# alu.net
KiCad netlist of a schematic drawn in EAGLE
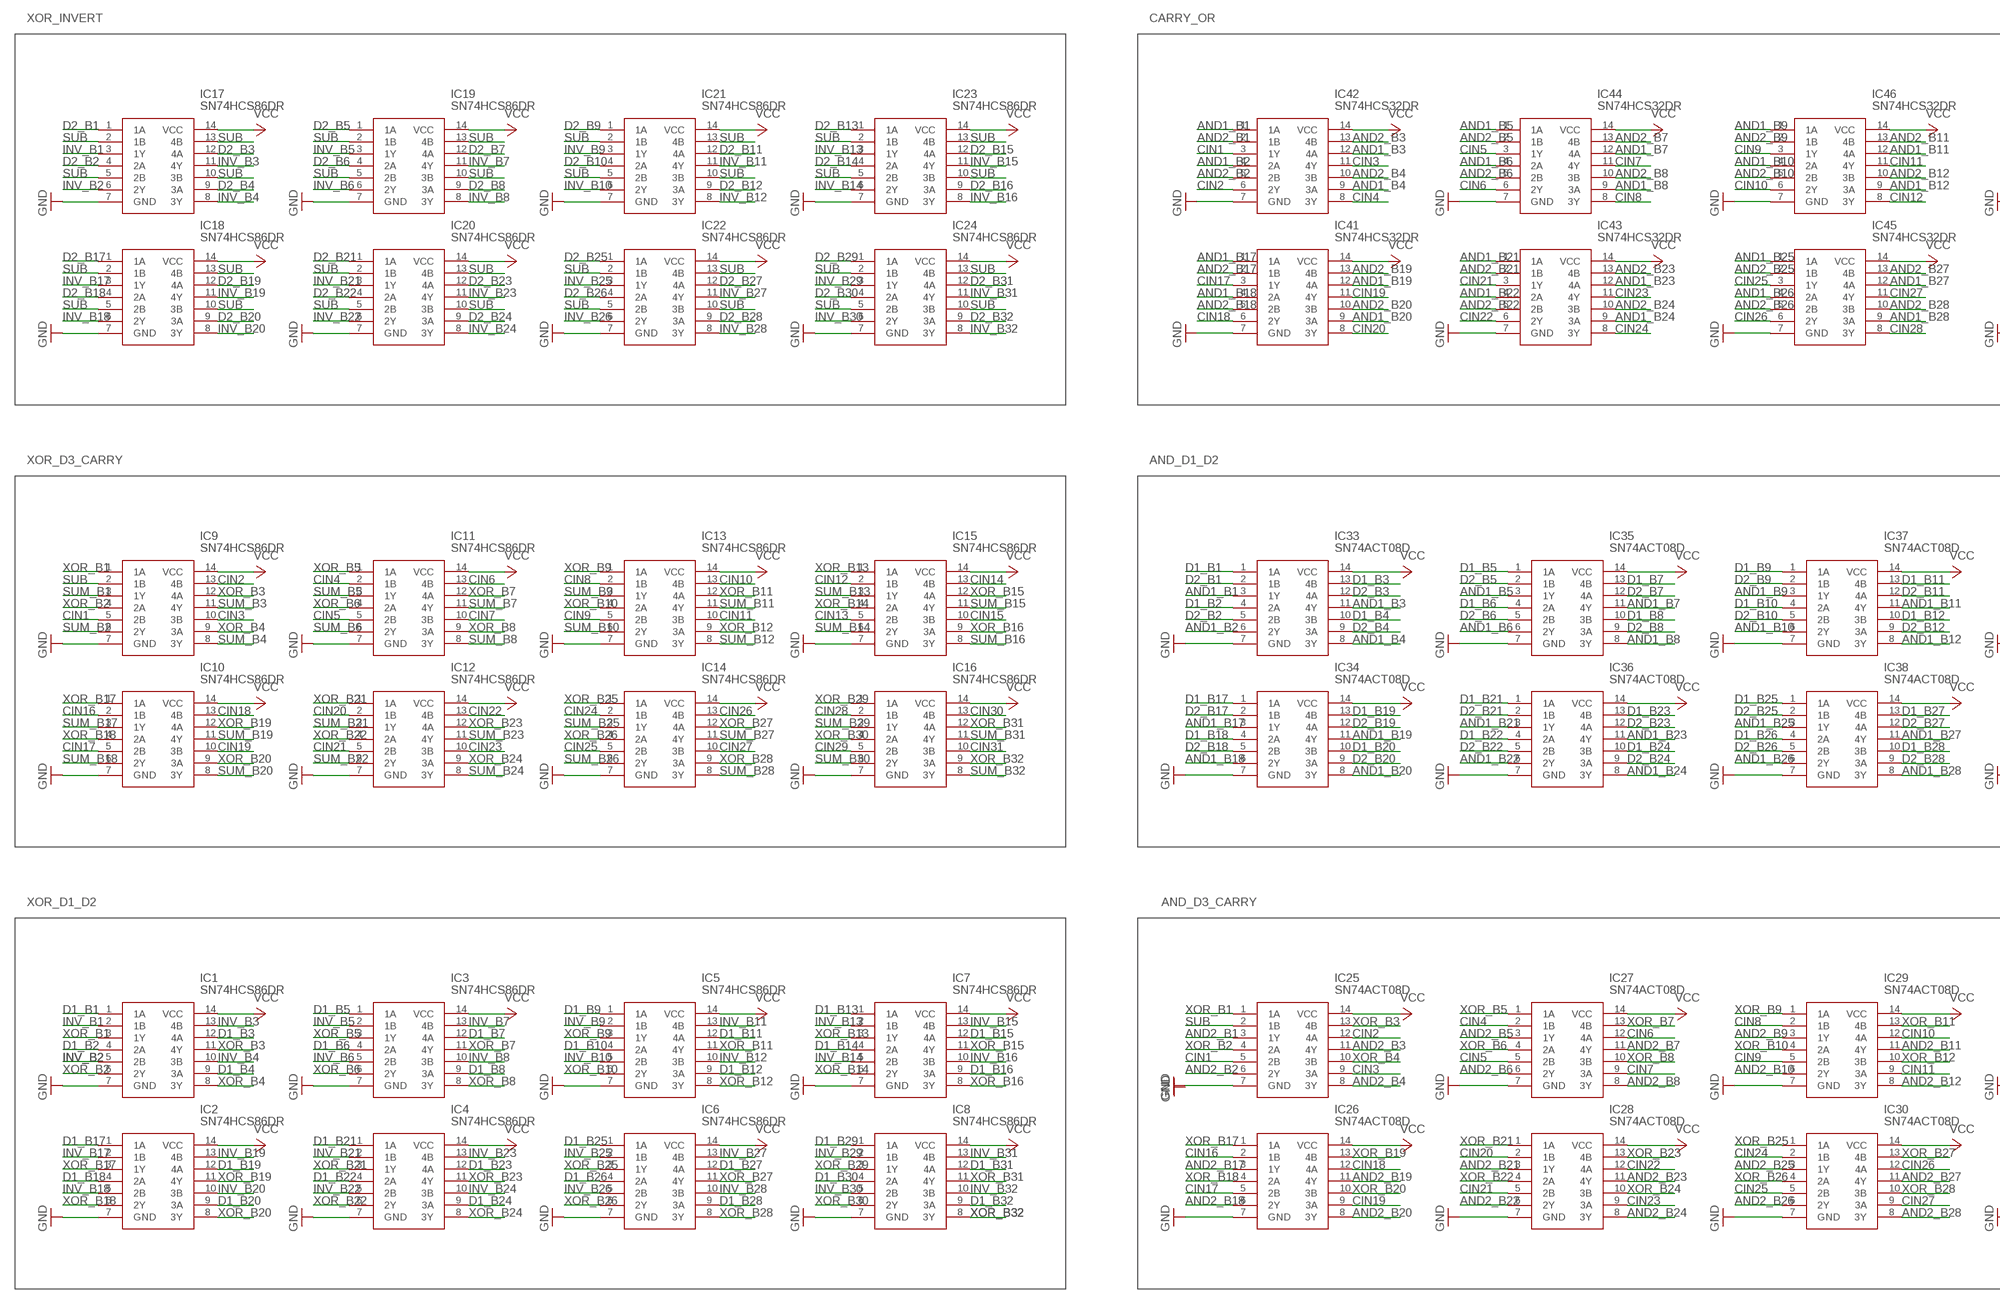
[diagram p0: schematic, sheet 1, part 1 of 2]
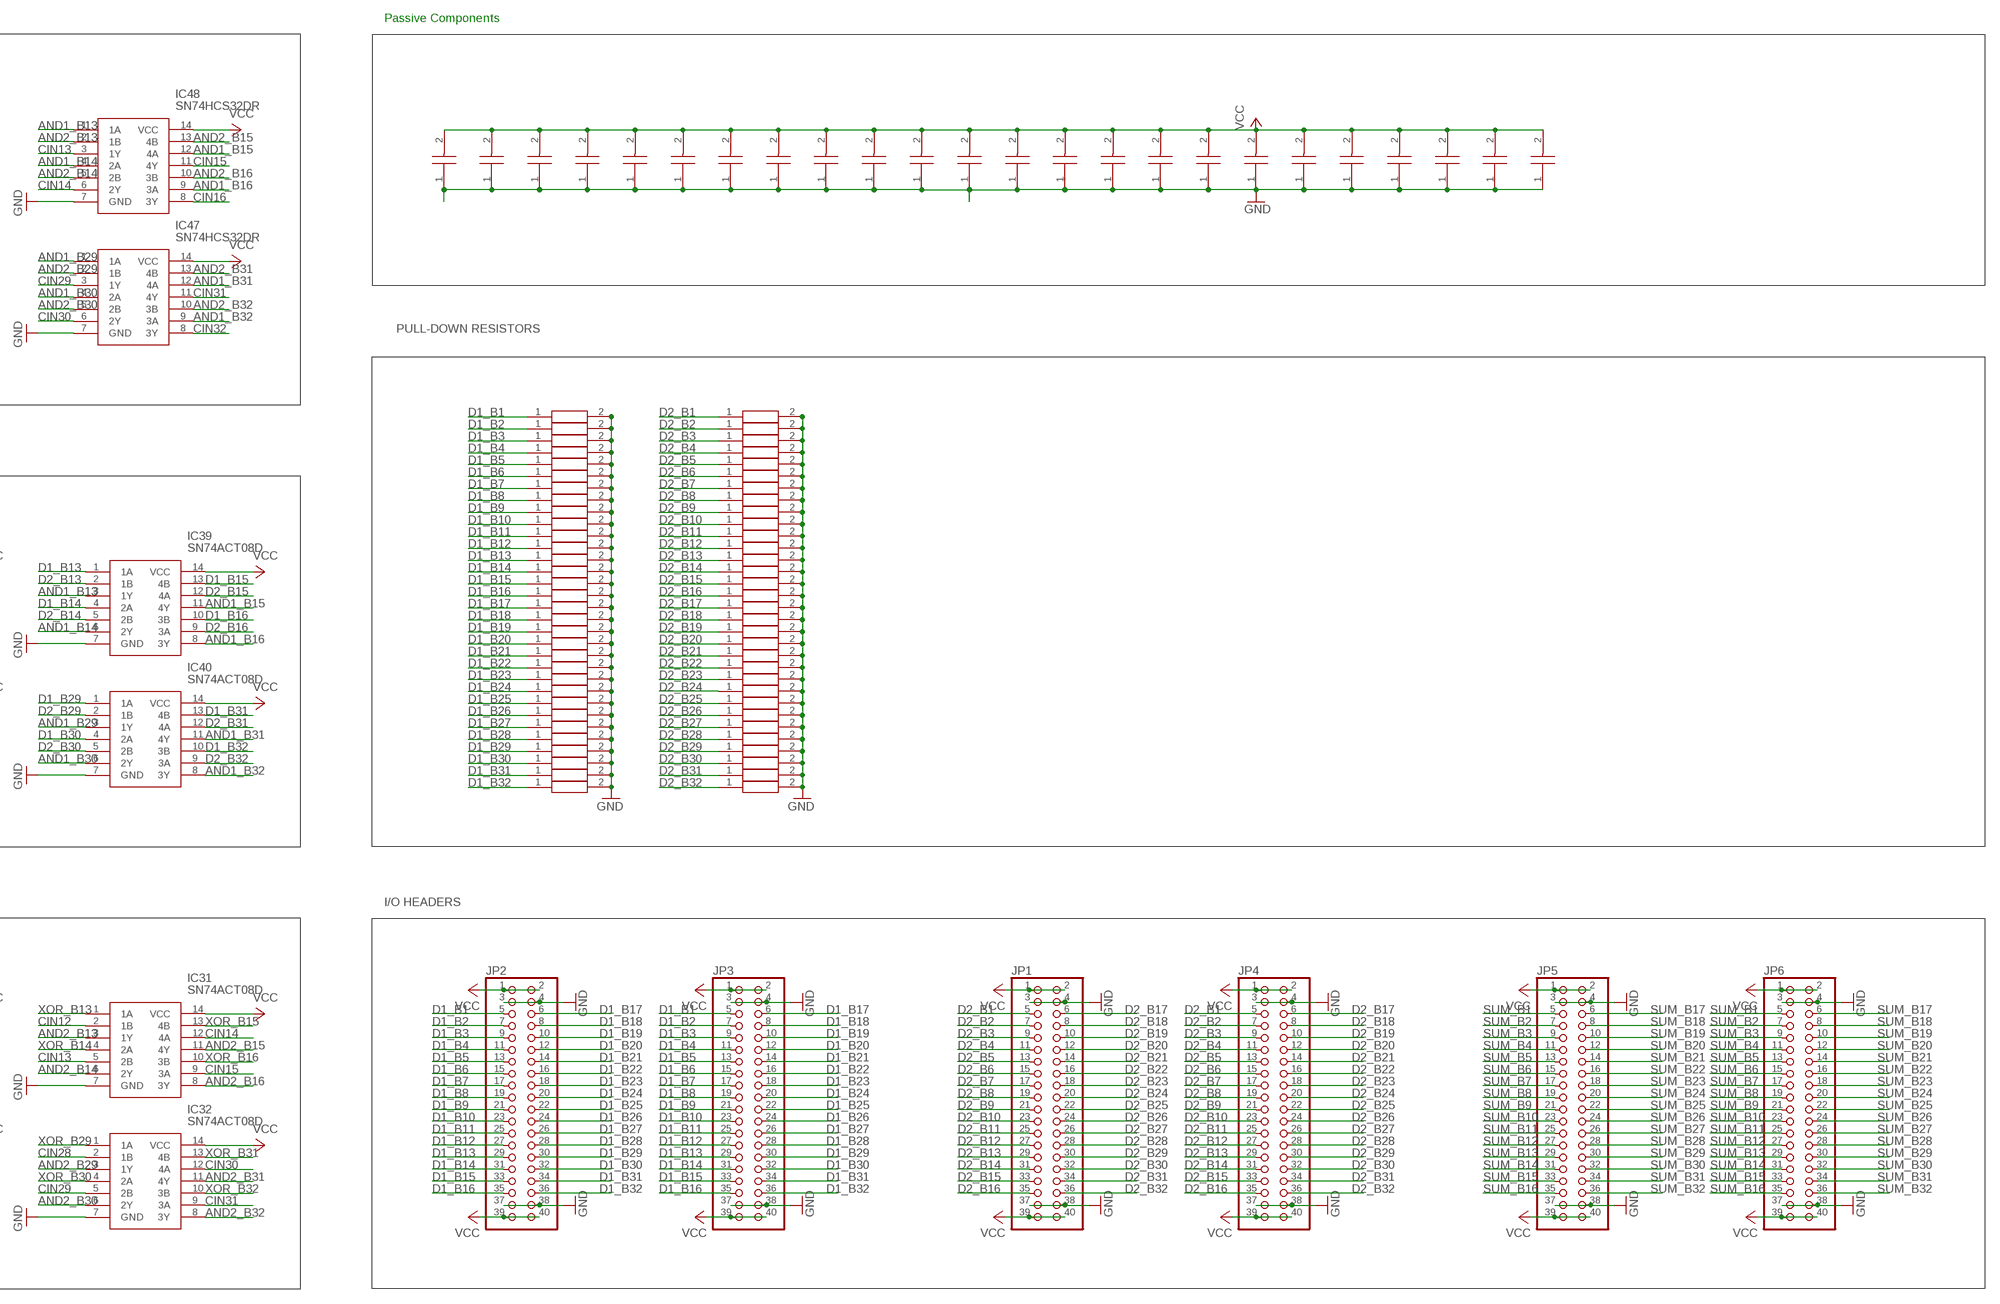
[diagram p1: schematic, sheet 1, part 2 of 2]

(export (version "E")
  (design (tool "Eeschema 10.0.6"))
  (components
    (comp (ref "C1")
      (value "CC0603KRX7R9BB104")
      (footprint "eagle-import:CAPC1608X90N")
      (fields (field (name "MOUSER_PART_NUMBER") "603-CC603KRX7R9BB104"))
      (libsource (lib "eagle-import") (part "CC0603KRX7R9BB104"))
    )
    (comp (ref "C2")
      (value "CC0603KRX7R9BB104")
      (footprint "eagle-import:CAPC1608X90N")
      (fields (field (name "MOUSER_PART_NUMBER") "603-CC603KRX7R9BB104"))
      (libsource (lib "eagle-import") (part "CC0603KRX7R9BB104"))
    )
    (comp (ref "C3")
      (value "CC0603KRX7R9BB104")
      (footprint "eagle-import:CAPC1608X90N")
      (fields (field (name "MOUSER_PART_NUMBER") "603-CC603KRX7R9BB104"))
      (libsource (lib "eagle-import") (part "CC0603KRX7R9BB104"))
    )
    (comp (ref "C4")
      (value "CC0603KRX7R9BB104")
      (footprint "eagle-import:CAPC1608X90N")
      (fields (field (name "MOUSER_PART_NUMBER") "603-CC603KRX7R9BB104"))
      (libsource (lib "eagle-import") (part "CC0603KRX7R9BB104"))
    )
    (comp (ref "C5")
      (value "CC0603KRX7R9BB104")
      (footprint "eagle-import:CAPC1608X90N")
      (fields (field (name "MOUSER_PART_NUMBER") "603-CC603KRX7R9BB104"))
      (libsource (lib "eagle-import") (part "CC0603KRX7R9BB104"))
    )
    (comp (ref "C6")
      (value "CC0603KRX7R9BB104")
      (footprint "eagle-import:CAPC1608X90N")
      (fields (field (name "MOUSER_PART_NUMBER") "603-CC603KRX7R9BB104"))
      (libsource (lib "eagle-import") (part "CC0603KRX7R9BB104"))
    )
    (comp (ref "C7")
      (value "CC0603KRX7R9BB104")
      (footprint "eagle-import:CAPC1608X90N")
      (fields (field (name "MOUSER_PART_NUMBER") "603-CC603KRX7R9BB104"))
      (libsource (lib "eagle-import") (part "CC0603KRX7R9BB104"))
    )
    (comp (ref "C8")
      (value "CC0603KRX7R9BB104")
      (footprint "eagle-import:CAPC1608X90N")
      (fields (field (name "MOUSER_PART_NUMBER") "603-CC603KRX7R9BB104"))
      (libsource (lib "eagle-import") (part "CC0603KRX7R9BB104"))
    )
    (comp (ref "C9")
      (value "CC0603KRX7R9BB104")
      (footprint "eagle-import:CAPC1608X90N")
      (fields (field (name "MOUSER_PART_NUMBER") "603-CC603KRX7R9BB104"))
      (libsource (lib "eagle-import") (part "CC0603KRX7R9BB104"))
    )
    (comp (ref "C10")
      (value "CC0603KRX7R9BB104")
      (footprint "eagle-import:CAPC1608X90N")
      (fields (field (name "MOUSER_PART_NUMBER") "603-CC603KRX7R9BB104"))
      (libsource (lib "eagle-import") (part "CC0603KRX7R9BB104"))
    )
    (comp (ref "C11")
      (value "CC0603KRX7R9BB104")
      (footprint "eagle-import:CAPC1608X90N")
      (fields (field (name "MOUSER_PART_NUMBER") "603-CC603KRX7R9BB104"))
      (libsource (lib "eagle-import") (part "CC0603KRX7R9BB104"))
    )
    (comp (ref "C12")
      (value "CC0603KRX7R9BB104")
      (footprint "eagle-import:CAPC1608X90N")
      (fields (field (name "MOUSER_PART_NUMBER") "603-CC603KRX7R9BB104"))
      (libsource (lib "eagle-import") (part "CC0603KRX7R9BB104"))
    )
    (comp (ref "C13")
      (value "CC0603KRX7R9BB104")
      (footprint "eagle-import:CAPC1608X90N")
      (fields (field (name "MOUSER_PART_NUMBER") "603-CC603KRX7R9BB104"))
      (libsource (lib "eagle-import") (part "CC0603KRX7R9BB104"))
    )
    (comp (ref "C14")
      (value "CC0603KRX7R9BB104")
      (footprint "eagle-import:CAPC1608X90N")
      (fields (field (name "MOUSER_PART_NUMBER") "603-CC603KRX7R9BB104"))
      (libsource (lib "eagle-import") (part "CC0603KRX7R9BB104"))
    )
    (comp (ref "C15")
      (value "CC0603KRX7R9BB104")
      (footprint "eagle-import:CAPC1608X90N")
      (fields (field (name "MOUSER_PART_NUMBER") "603-CC603KRX7R9BB104"))
      (libsource (lib "eagle-import") (part "CC0603KRX7R9BB104"))
    )
    (comp (ref "C16")
      (value "CC0603KRX7R9BB104")
      (footprint "eagle-import:CAPC1608X90N")
      (fields (field (name "MOUSER_PART_NUMBER") "603-CC603KRX7R9BB104"))
      (libsource (lib "eagle-import") (part "CC0603KRX7R9BB104"))
    )
    (comp (ref "C17")
      (value "CC0603KRX7R9BB104")
      (footprint "eagle-import:CAPC1608X90N")
      (fields (field (name "MOUSER_PART_NUMBER") "603-CC603KRX7R9BB104"))
      (libsource (lib "eagle-import") (part "CC0603KRX7R9BB104"))
    )
    (comp (ref "C18")
      (value "CC0603KRX7R9BB104")
      (footprint "eagle-import:CAPC1608X90N")
      (fields (field (name "MOUSER_PART_NUMBER") "603-CC603KRX7R9BB104"))
      (libsource (lib "eagle-import") (part "CC0603KRX7R9BB104"))
    )
    (comp (ref "C19")
      (value "CC0603KRX7R9BB104")
      (footprint "eagle-import:CAPC1608X90N")
      (fields (field (name "MOUSER_PART_NUMBER") "603-CC603KRX7R9BB104"))
      (libsource (lib "eagle-import") (part "CC0603KRX7R9BB104"))
    )
    (comp (ref "C20")
      (value "CC0603KRX7R9BB104")
      (footprint "eagle-import:CAPC1608X90N")
      (fields (field (name "MOUSER_PART_NUMBER") "603-CC603KRX7R9BB104"))
      (libsource (lib "eagle-import") (part "CC0603KRX7R9BB104"))
    )
    (comp (ref "C21")
      (value "CC0603KRX7R9BB104")
      (footprint "eagle-import:CAPC1608X90N")
      (fields (field (name "MOUSER_PART_NUMBER") "603-CC603KRX7R9BB104"))
      (libsource (lib "eagle-import") (part "CC0603KRX7R9BB104"))
    )
    (comp (ref "C22")
      (value "CC0603KRX7R9BB104")
      (footprint "eagle-import:CAPC1608X90N")
      (fields (field (name "MOUSER_PART_NUMBER") "603-CC603KRX7R9BB104"))
      (libsource (lib "eagle-import") (part "CC0603KRX7R9BB104"))
    )
    (comp (ref "C23")
      (value "CC0603KRX7R9BB104")
      (footprint "eagle-import:CAPC1608X90N")
      (fields (field (name "MOUSER_PART_NUMBER") "603-CC603KRX7R9BB104"))
      (libsource (lib "eagle-import") (part "CC0603KRX7R9BB104"))
    )
    (comp (ref "C24")
      (value "CC0603KRX7R9BB104")
      (footprint "eagle-import:CAPC1608X90N")
      (fields (field (name "MOUSER_PART_NUMBER") "603-CC603KRX7R9BB104"))
      (libsource (lib "eagle-import") (part "CC0603KRX7R9BB104"))
    )
    (comp (ref "IC1")
      (value "SN74HCS86DR")
      (footprint "eagle-import:SOIC127P600X175-14N")
      (fields (field (name "MOUSER_PART_NUMBER") "595-SN74HCS86DR"))
      (libsource (lib "eagle-import") (part "SN74HCS86DR"))
    )
    (comp (ref "IC2")
      (value "SN74HCS86DR")
      (footprint "eagle-import:SOIC127P600X175-14N")
      (fields (field (name "MOUSER_PART_NUMBER") "595-SN74HCS86DR"))
      (libsource (lib "eagle-import") (part "SN74HCS86DR"))
    )
    (comp (ref "IC3")
      (value "SN74HCS86DR")
      (footprint "eagle-import:SOIC127P600X175-14N")
      (fields (field (name "MOUSER_PART_NUMBER") "595-SN74HCS86DR"))
      (libsource (lib "eagle-import") (part "SN74HCS86DR"))
    )
    (comp (ref "IC4")
      (value "SN74HCS86DR")
      (footprint "eagle-import:SOIC127P600X175-14N")
      (fields (field (name "MOUSER_PART_NUMBER") "595-SN74HCS86DR"))
      (libsource (lib "eagle-import") (part "SN74HCS86DR"))
    )
    (comp (ref "IC5")
      (value "SN74HCS86DR")
      (footprint "eagle-import:SOIC127P600X175-14N")
      (fields (field (name "MOUSER_PART_NUMBER") "595-SN74HCS86DR"))
      (libsource (lib "eagle-import") (part "SN74HCS86DR"))
    )
    (comp (ref "IC6")
      (value "SN74HCS86DR")
      (footprint "eagle-import:SOIC127P600X175-14N")
      (fields (field (name "MOUSER_PART_NUMBER") "595-SN74HCS86DR"))
      (libsource (lib "eagle-import") (part "SN74HCS86DR"))
    )
    (comp (ref "IC7")
      (value "SN74HCS86DR")
      (footprint "eagle-import:SOIC127P600X175-14N")
      (fields (field (name "MOUSER_PART_NUMBER") "595-SN74HCS86DR"))
      (libsource (lib "eagle-import") (part "SN74HCS86DR"))
    )
    (comp (ref "IC8")
      (value "SN74HCS86DR")
      (footprint "eagle-import:SOIC127P600X175-14N")
      (fields (field (name "MOUSER_PART_NUMBER") "595-SN74HCS86DR"))
      (libsource (lib "eagle-import") (part "SN74HCS86DR"))
    )
    (comp (ref "IC9")
      (value "SN74HCS86DR")
      (footprint "eagle-import:SOIC127P600X175-14N")
      (fields (field (name "MOUSER_PART_NUMBER") "595-SN74HCS86DR"))
      (libsource (lib "eagle-import") (part "SN74HCS86DR"))
    )
    (comp (ref "IC10")
      (value "SN74HCS86DR")
      (footprint "eagle-import:SOIC127P600X175-14N")
      (fields (field (name "MOUSER_PART_NUMBER") "595-SN74HCS86DR"))
      (libsource (lib "eagle-import") (part "SN74HCS86DR"))
    )
    (comp (ref "IC11")
      (value "SN74HCS86DR")
      (footprint "eagle-import:SOIC127P600X175-14N")
      (fields (field (name "MOUSER_PART_NUMBER") "595-SN74HCS86DR"))
      (libsource (lib "eagle-import") (part "SN74HCS86DR"))
    )
    (comp (ref "IC12")
      (value "SN74HCS86DR")
      (footprint "eagle-import:SOIC127P600X175-14N")
      (fields (field (name "MOUSER_PART_NUMBER") "595-SN74HCS86DR"))
      (libsource (lib "eagle-import") (part "SN74HCS86DR"))
    )
    (comp (ref "IC13")
      (value "SN74HCS86DR")
      (footprint "eagle-import:SOIC127P600X175-14N")
      (fields (field (name "MOUSER_PART_NUMBER") "595-SN74HCS86DR"))
      (libsource (lib "eagle-import") (part "SN74HCS86DR"))
    )
    (comp (ref "IC14")
      (value "SN74HCS86DR")
      (footprint "eagle-import:SOIC127P600X175-14N")
      (fields (field (name "MOUSER_PART_NUMBER") "595-SN74HCS86DR"))
      (libsource (lib "eagle-import") (part "SN74HCS86DR"))
    )
    (comp (ref "IC15")
      (value "SN74HCS86DR")
      (footprint "eagle-import:SOIC127P600X175-14N")
      (fields (field (name "MOUSER_PART_NUMBER") "595-SN74HCS86DR"))
      (libsource (lib "eagle-import") (part "SN74HCS86DR"))
    )
    (comp (ref "IC16")
      (value "SN74HCS86DR")
      (footprint "eagle-import:SOIC127P600X175-14N")
      (fields (field (name "MOUSER_PART_NUMBER") "595-SN74HCS86DR"))
      (libsource (lib "eagle-import") (part "SN74HCS86DR"))
    )
    (comp (ref "IC17")
      (value "SN74HCS86DR")
      (footprint "eagle-import:SOIC127P600X175-14N")
      (fields (field (name "MOUSER_PART_NUMBER") "595-SN74HCS86DR"))
      (libsource (lib "eagle-import") (part "SN74HCS86DR"))
    )
    (comp (ref "IC18")
      (value "SN74HCS86DR")
      (footprint "eagle-import:SOIC127P600X175-14N")
      (fields (field (name "MOUSER_PART_NUMBER") "595-SN74HCS86DR"))
      (libsource (lib "eagle-import") (part "SN74HCS86DR"))
    )
    (comp (ref "IC19")
      (value "SN74HCS86DR")
      (footprint "eagle-import:SOIC127P600X175-14N")
      (fields (field (name "MOUSER_PART_NUMBER") "595-SN74HCS86DR"))
      (libsource (lib "eagle-import") (part "SN74HCS86DR"))
    )
    (comp (ref "IC20")
      (value "SN74HCS86DR")
      (footprint "eagle-import:SOIC127P600X175-14N")
      (fields (field (name "MOUSER_PART_NUMBER") "595-SN74HCS86DR"))
      (libsource (lib "eagle-import") (part "SN74HCS86DR"))
    )
    (comp (ref "IC21")
      (value "SN74HCS86DR")
      (footprint "eagle-import:SOIC127P600X175-14N")
      (fields (field (name "MOUSER_PART_NUMBER") "595-SN74HCS86DR"))
      (libsource (lib "eagle-import") (part "SN74HCS86DR"))
    )
    (comp (ref "IC22")
      (value "SN74HCS86DR")
      (footprint "eagle-import:SOIC127P600X175-14N")
      (fields (field (name "MOUSER_PART_NUMBER") "595-SN74HCS86DR"))
      (libsource (lib "eagle-import") (part "SN74HCS86DR"))
    )
    (comp (ref "IC23")
      (value "SN74HCS86DR")
      (footprint "eagle-import:SOIC127P600X175-14N")
      (fields (field (name "MOUSER_PART_NUMBER") "595-SN74HCS86DR"))
      (libsource (lib "eagle-import") (part "SN74HCS86DR"))
    )
    (comp (ref "IC24")
      (value "SN74HCS86DR")
      (footprint "eagle-import:SOIC127P600X175-14N")
      (fields (field (name "MOUSER_PART_NUMBER") "595-SN74HCS86DR"))
      (libsource (lib "eagle-import") (part "SN74HCS86DR"))
    )
    (comp (ref "IC25")
      (value "SN74ACT08D")
      (footprint "eagle-import:SOIC127P600X175-14N")
      (fields (field (name "MOUSER_PART_NUMBER") "595-SN74ACT08D"))
      (libsource (lib "eagle-import") (part "SN74ACT08D"))
    )
    (comp (ref "IC26")
      (value "SN74ACT08D")
      (footprint "eagle-import:SOIC127P600X175-14N")
      (fields (field (name "MOUSER_PART_NUMBER") "595-SN74ACT08D"))
      (libsource (lib "eagle-import") (part "SN74ACT08D"))
    )
    (comp (ref "IC27")
      (value "SN74ACT08D")
      (footprint "eagle-import:SOIC127P600X175-14N")
      (fields (field (name "MOUSER_PART_NUMBER") "595-SN74ACT08D"))
      (libsource (lib "eagle-import") (part "SN74ACT08D"))
    )
    (comp (ref "IC28")
      (value "SN74ACT08D")
      (footprint "eagle-import:SOIC127P600X175-14N")
      (fields (field (name "MOUSER_PART_NUMBER") "595-SN74ACT08D"))
      (libsource (lib "eagle-import") (part "SN74ACT08D"))
    )
    (comp (ref "IC29")
      (value "SN74ACT08D")
      (footprint "eagle-import:SOIC127P600X175-14N")
      (fields (field (name "MOUSER_PART_NUMBER") "595-SN74ACT08D"))
      (libsource (lib "eagle-import") (part "SN74ACT08D"))
    )
    (comp (ref "IC30")
      (value "SN74ACT08D")
      (footprint "eagle-import:SOIC127P600X175-14N")
      (fields (field (name "MOUSER_PART_NUMBER") "595-SN74ACT08D"))
      (libsource (lib "eagle-import") (part "SN74ACT08D"))
    )
    (comp (ref "IC31")
      (value "SN74ACT08D")
      (footprint "eagle-import:SOIC127P600X175-14N")
      (fields (field (name "MOUSER_PART_NUMBER") "595-SN74ACT08D"))
      (libsource (lib "eagle-import") (part "SN74ACT08D"))
    )
    (comp (ref "IC32")
      (value "SN74ACT08D")
      (footprint "eagle-import:SOIC127P600X175-14N")
      (fields (field (name "MOUSER_PART_NUMBER") "595-SN74ACT08D"))
      (libsource (lib "eagle-import") (part "SN74ACT08D"))
    )
    (comp (ref "IC33")
      (value "SN74ACT08D")
      (footprint "eagle-import:SOIC127P600X175-14N")
      (fields (field (name "MOUSER_PART_NUMBER") "595-SN74ACT08D"))
      (libsource (lib "eagle-import") (part "SN74ACT08D"))
    )
    (comp (ref "IC34")
      (value "SN74ACT08D")
      (footprint "eagle-import:SOIC127P600X175-14N")
      (fields (field (name "MOUSER_PART_NUMBER") "595-SN74ACT08D"))
      (libsource (lib "eagle-import") (part "SN74ACT08D"))
    )
    (comp (ref "IC35")
      (value "SN74ACT08D")
      (footprint "eagle-import:SOIC127P600X175-14N")
      (fields (field (name "MOUSER_PART_NUMBER") "595-SN74ACT08D"))
      (libsource (lib "eagle-import") (part "SN74ACT08D"))
    )
    (comp (ref "IC36")
      (value "SN74ACT08D")
      (footprint "eagle-import:SOIC127P600X175-14N")
      (fields (field (name "MOUSER_PART_NUMBER") "595-SN74ACT08D"))
      (libsource (lib "eagle-import") (part "SN74ACT08D"))
    )
    (comp (ref "IC37")
      (value "SN74ACT08D")
      (footprint "eagle-import:SOIC127P600X175-14N")
      (fields (field (name "MOUSER_PART_NUMBER") "595-SN74ACT08D"))
      (libsource (lib "eagle-import") (part "SN74ACT08D"))
    )
    (comp (ref "IC38")
      (value "SN74ACT08D")
      (footprint "eagle-import:SOIC127P600X175-14N")
      (fields (field (name "MOUSER_PART_NUMBER") "595-SN74ACT08D"))
      (libsource (lib "eagle-import") (part "SN74ACT08D"))
    )
    (comp (ref "IC39")
      (value "SN74ACT08D")
      (footprint "eagle-import:SOIC127P600X175-14N")
      (fields (field (name "MOUSER_PART_NUMBER") "595-SN74ACT08D"))
      (libsource (lib "eagle-import") (part "SN74ACT08D"))
    )
    (comp (ref "IC40")
      (value "SN74ACT08D")
      (footprint "eagle-import:SOIC127P600X175-14N")
      (fields (field (name "MOUSER_PART_NUMBER") "595-SN74ACT08D"))
      (libsource (lib "eagle-import") (part "SN74ACT08D"))
    )
    (comp (ref "IC41")
      (value "SN74HCS32DR")
      (footprint "eagle-import:SOIC127P600X175-14N")
      (fields (field (name "MOUSER_PART_NUMBER") "595-SN74HCS32DR"))
      (libsource (lib "eagle-import") (part "SN74HCS32DR"))
    )
    (comp (ref "IC42")
      (value "SN74HCS32DR")
      (footprint "eagle-import:SOIC127P600X175-14N")
      (fields (field (name "MOUSER_PART_NUMBER") "595-SN74HCS32DR"))
      (libsource (lib "eagle-import") (part "SN74HCS32DR"))
    )
    (comp (ref "IC43")
      (value "SN74HCS32DR")
      (footprint "eagle-import:SOIC127P600X175-14N")
      (fields (field (name "MOUSER_PART_NUMBER") "595-SN74HCS32DR"))
      (libsource (lib "eagle-import") (part "SN74HCS32DR"))
    )
    (comp (ref "IC44")
      (value "SN74HCS32DR")
      (footprint "eagle-import:SOIC127P600X175-14N")
      (fields (field (name "MOUSER_PART_NUMBER") "595-SN74HCS32DR"))
      (libsource (lib "eagle-import") (part "SN74HCS32DR"))
    )
    (comp (ref "IC45")
      (value "SN74HCS32DR")
      (footprint "eagle-import:SOIC127P600X175-14N")
      (fields (field (name "MOUSER_PART_NUMBER") "595-SN74HCS32DR"))
      (libsource (lib "eagle-import") (part "SN74HCS32DR"))
    )
    (comp (ref "IC46")
      (value "SN74HCS32DR")
      (footprint "eagle-import:SOIC127P600X175-14N")
      (fields (field (name "MOUSER_PART_NUMBER") "595-SN74HCS32DR"))
      (libsource (lib "eagle-import") (part "SN74HCS32DR"))
    )
    (comp (ref "IC47")
      (value "SN74HCS32DR")
      (footprint "eagle-import:SOIC127P600X175-14N")
      (fields (field (name "MOUSER_PART_NUMBER") "595-SN74HCS32DR"))
      (libsource (lib "eagle-import") (part "SN74HCS32DR"))
    )
    (comp (ref "IC48")
      (value "SN74HCS32DR")
      (footprint "eagle-import:SOIC127P600X175-14N")
      (fields (field (name "MOUSER_PART_NUMBER") "595-SN74HCS32DR"))
      (libsource (lib "eagle-import") (part "SN74HCS32DR"))
    )
    (comp (ref "JP1")
      (value "PINHD-2X20")
      (footprint "eagle-import:2X20")
      (libsource (lib "eagle-import") (part "PINHD-2X20"))
    )
    (comp (ref "JP2")
      (value "PINHD-2X20")
      (footprint "eagle-import:2X20")
      (libsource (lib "eagle-import") (part "PINHD-2X20"))
    )
    (comp (ref "JP3")
      (value "PINHD-2X20")
      (footprint "eagle-import:2X20")
      (libsource (lib "eagle-import") (part "PINHD-2X20"))
    )
    (comp (ref "JP4")
      (value "PINHD-2X20")
      (footprint "eagle-import:2X20")
      (libsource (lib "eagle-import") (part "PINHD-2X20"))
    )
    (comp (ref "JP5")
      (value "PINHD-2X20")
      (footprint "eagle-import:2X20")
      (libsource (lib "eagle-import") (part "PINHD-2X20"))
    )
    (comp (ref "JP6")
      (value "PINHD-2X20")
      (footprint "eagle-import:2X20")
      (libsource (lib "eagle-import") (part "PINHD-2X20"))
    )
    (comp (ref "R1")
      (value "RC0603FR-0710KL")
      (footprint "eagle-import:RESC1608X55N")
      (fields (field (name "MOUSER_PART_NUMBER") "603-RC0603FR-0710KL"))
      (libsource (lib "eagle-import") (part "RC0603FR-0710KL"))
    )
    (comp (ref "R2")
      (value "RC0603FR-0710KL")
      (footprint "eagle-import:RESC1608X55N")
      (fields (field (name "MOUSER_PART_NUMBER") "603-RC0603FR-0710KL"))
      (libsource (lib "eagle-import") (part "RC0603FR-0710KL"))
    )
    (comp (ref "R3")
      (value "RC0603FR-0710KL")
      (footprint "eagle-import:RESC1608X55N")
      (fields (field (name "MOUSER_PART_NUMBER") "603-RC0603FR-0710KL"))
      (libsource (lib "eagle-import") (part "RC0603FR-0710KL"))
    )
    (comp (ref "R4")
      (value "RC0603FR-0710KL")
      (footprint "eagle-import:RESC1608X55N")
      (fields (field (name "MOUSER_PART_NUMBER") "603-RC0603FR-0710KL"))
      (libsource (lib "eagle-import") (part "RC0603FR-0710KL"))
    )
    (comp (ref "R5")
      (value "RC0603FR-0710KL")
      (footprint "eagle-import:RESC1608X55N")
      (fields (field (name "MOUSER_PART_NUMBER") "603-RC0603FR-0710KL"))
      (libsource (lib "eagle-import") (part "RC0603FR-0710KL"))
    )
    (comp (ref "R6")
      (value "RC0603FR-0710KL")
      (footprint "eagle-import:RESC1608X55N")
      (fields (field (name "MOUSER_PART_NUMBER") "603-RC0603FR-0710KL"))
      (libsource (lib "eagle-import") (part "RC0603FR-0710KL"))
    )
    (comp (ref "R7")
      (value "RC0603FR-0710KL")
      (footprint "eagle-import:RESC1608X55N")
      (fields (field (name "MOUSER_PART_NUMBER") "603-RC0603FR-0710KL"))
      (libsource (lib "eagle-import") (part "RC0603FR-0710KL"))
    )
    (comp (ref "R8")
      (value "RC0603FR-0710KL")
      (footprint "eagle-import:RESC1608X55N")
      (fields (field (name "MOUSER_PART_NUMBER") "603-RC0603FR-0710KL"))
      (libsource (lib "eagle-import") (part "RC0603FR-0710KL"))
    )
    (comp (ref "R9")
      (value "RC0603FR-0710KL")
      (footprint "eagle-import:RESC1608X55N")
      (fields (field (name "MOUSER_PART_NUMBER") "603-RC0603FR-0710KL"))
      (libsource (lib "eagle-import") (part "RC0603FR-0710KL"))
    )
    (comp (ref "R10")
      (value "RC0603FR-0710KL")
      (footprint "eagle-import:RESC1608X55N")
      (fields (field (name "MOUSER_PART_NUMBER") "603-RC0603FR-0710KL"))
      (libsource (lib "eagle-import") (part "RC0603FR-0710KL"))
    )
    (comp (ref "R11")
      (value "RC0603FR-0710KL")
      (footprint "eagle-import:RESC1608X55N")
      (fields (field (name "MOUSER_PART_NUMBER") "603-RC0603FR-0710KL"))
      (libsource (lib "eagle-import") (part "RC0603FR-0710KL"))
    )
    (comp (ref "R12")
      (value "RC0603FR-0710KL")
      (footprint "eagle-import:RESC1608X55N")
      (fields (field (name "MOUSER_PART_NUMBER") "603-RC0603FR-0710KL"))
      (libsource (lib "eagle-import") (part "RC0603FR-0710KL"))
    )
    (comp (ref "R13")
      (value "RC0603FR-0710KL")
      (footprint "eagle-import:RESC1608X55N")
      (fields (field (name "MOUSER_PART_NUMBER") "603-RC0603FR-0710KL"))
      (libsource (lib "eagle-import") (part "RC0603FR-0710KL"))
    )
    (comp (ref "R14")
      (value "RC0603FR-0710KL")
      (footprint "eagle-import:RESC1608X55N")
      (fields (field (name "MOUSER_PART_NUMBER") "603-RC0603FR-0710KL"))
      (libsource (lib "eagle-import") (part "RC0603FR-0710KL"))
    )
    (comp (ref "R15")
      (value "RC0603FR-0710KL")
      (footprint "eagle-import:RESC1608X55N")
      (fields (field (name "MOUSER_PART_NUMBER") "603-RC0603FR-0710KL"))
      (libsource (lib "eagle-import") (part "RC0603FR-0710KL"))
    )
    (comp (ref "R16")
      (value "RC0603FR-0710KL")
      (footprint "eagle-import:RESC1608X55N")
      (fields (field (name "MOUSER_PART_NUMBER") "603-RC0603FR-0710KL"))
      (libsource (lib "eagle-import") (part "RC0603FR-0710KL"))
    )
    (comp (ref "R17")
      (value "RC0603FR-0710KL")
      (footprint "eagle-import:RESC1608X55N")
      (fields (field (name "MOUSER_PART_NUMBER") "603-RC0603FR-0710KL"))
      (libsource (lib "eagle-import") (part "RC0603FR-0710KL"))
    )
    (comp (ref "R18")
      (value "RC0603FR-0710KL")
      (footprint "eagle-import:RESC1608X55N")
      (fields (field (name "MOUSER_PART_NUMBER") "603-RC0603FR-0710KL"))
      (libsource (lib "eagle-import") (part "RC0603FR-0710KL"))
    )
    (comp (ref "R19")
      (value "RC0603FR-0710KL")
      (footprint "eagle-import:RESC1608X55N")
      (fields (field (name "MOUSER_PART_NUMBER") "603-RC0603FR-0710KL"))
      (libsource (lib "eagle-import") (part "RC0603FR-0710KL"))
    )
    (comp (ref "R20")
      (value "RC0603FR-0710KL")
      (footprint "eagle-import:RESC1608X55N")
      (fields (field (name "MOUSER_PART_NUMBER") "603-RC0603FR-0710KL"))
      (libsource (lib "eagle-import") (part "RC0603FR-0710KL"))
    )
    (comp (ref "R21")
      (value "RC0603FR-0710KL")
      (footprint "eagle-import:RESC1608X55N")
      (fields (field (name "MOUSER_PART_NUMBER") "603-RC0603FR-0710KL"))
      (libsource (lib "eagle-import") (part "RC0603FR-0710KL"))
    )
    (comp (ref "R22")
      (value "RC0603FR-0710KL")
      (footprint "eagle-import:RESC1608X55N")
      (fields (field (name "MOUSER_PART_NUMBER") "603-RC0603FR-0710KL"))
      (libsource (lib "eagle-import") (part "RC0603FR-0710KL"))
    )
    (comp (ref "R23")
      (value "RC0603FR-0710KL")
      (footprint "eagle-import:RESC1608X55N")
      (fields (field (name "MOUSER_PART_NUMBER") "603-RC0603FR-0710KL"))
      (libsource (lib "eagle-import") (part "RC0603FR-0710KL"))
    )
    (comp (ref "R24")
      (value "RC0603FR-0710KL")
      (footprint "eagle-import:RESC1608X55N")
      (fields (field (name "MOUSER_PART_NUMBER") "603-RC0603FR-0710KL"))
      (libsource (lib "eagle-import") (part "RC0603FR-0710KL"))
    )
    (comp (ref "R25")
      (value "RC0603FR-0710KL")
      (footprint "eagle-import:RESC1608X55N")
      (fields (field (name "MOUSER_PART_NUMBER") "603-RC0603FR-0710KL"))
      (libsource (lib "eagle-import") (part "RC0603FR-0710KL"))
    )
    (comp (ref "R26")
      (value "RC0603FR-0710KL")
      (footprint "eagle-import:RESC1608X55N")
      (fields (field (name "MOUSER_PART_NUMBER") "603-RC0603FR-0710KL"))
      (libsource (lib "eagle-import") (part "RC0603FR-0710KL"))
    )
    (comp (ref "R27")
      (value "RC0603FR-0710KL")
      (footprint "eagle-import:RESC1608X55N")
      (fields (field (name "MOUSER_PART_NUMBER") "603-RC0603FR-0710KL"))
      (libsource (lib "eagle-import") (part "RC0603FR-0710KL"))
    )
    (comp (ref "R28")
      (value "RC0603FR-0710KL")
      (footprint "eagle-import:RESC1608X55N")
      (fields (field (name "MOUSER_PART_NUMBER") "603-RC0603FR-0710KL"))
      (libsource (lib "eagle-import") (part "RC0603FR-0710KL"))
    )
    (comp (ref "R29")
      (value "RC0603FR-0710KL")
      (footprint "eagle-import:RESC1608X55N")
      (fields (field (name "MOUSER_PART_NUMBER") "603-RC0603FR-0710KL"))
      (libsource (lib "eagle-import") (part "RC0603FR-0710KL"))
    )
    (comp (ref "R30")
      (value "RC0603FR-0710KL")
      (footprint "eagle-import:RESC1608X55N")
      (fields (field (name "MOUSER_PART_NUMBER") "603-RC0603FR-0710KL"))
      (libsource (lib "eagle-import") (part "RC0603FR-0710KL"))
    )
    (comp (ref "R31")
      (value "RC0603FR-0710KL")
      (footprint "eagle-import:RESC1608X55N")
      (fields (field (name "MOUSER_PART_NUMBER") "603-RC0603FR-0710KL"))
      (libsource (lib "eagle-import") (part "RC0603FR-0710KL"))
    )
    (comp (ref "R32")
      (value "RC0603FR-0710KL")
      (footprint "eagle-import:RESC1608X55N")
      (fields (field (name "MOUSER_PART_NUMBER") "603-RC0603FR-0710KL"))
      (libsource (lib "eagle-import") (part "RC0603FR-0710KL"))
    )
    (comp (ref "R33")
      (value "RC0603FR-0710KL")
      (footprint "eagle-import:RESC1608X55N")
      (fields (field (name "MOUSER_PART_NUMBER") "603-RC0603FR-0710KL"))
      (libsource (lib "eagle-import") (part "RC0603FR-0710KL"))
    )
    (comp (ref "R34")
      (value "RC0603FR-0710KL")
      (footprint "eagle-import:RESC1608X55N")
      (fields (field (name "MOUSER_PART_NUMBER") "603-RC0603FR-0710KL"))
      (libsource (lib "eagle-import") (part "RC0603FR-0710KL"))
    )
    (comp (ref "R35")
      (value "RC0603FR-0710KL")
      (footprint "eagle-import:RESC1608X55N")
      (fields (field (name "MOUSER_PART_NUMBER") "603-RC0603FR-0710KL"))
      (libsource (lib "eagle-import") (part "RC0603FR-0710KL"))
    )
    (comp (ref "R36")
      (value "RC0603FR-0710KL")
      (footprint "eagle-import:RESC1608X55N")
      (fields (field (name "MOUSER_PART_NUMBER") "603-RC0603FR-0710KL"))
      (libsource (lib "eagle-import") (part "RC0603FR-0710KL"))
    )
    (comp (ref "R37")
      (value "RC0603FR-0710KL")
      (footprint "eagle-import:RESC1608X55N")
      (fields (field (name "MOUSER_PART_NUMBER") "603-RC0603FR-0710KL"))
      (libsource (lib "eagle-import") (part "RC0603FR-0710KL"))
    )
    (comp (ref "R38")
      (value "RC0603FR-0710KL")
      (footprint "eagle-import:RESC1608X55N")
      (fields (field (name "MOUSER_PART_NUMBER") "603-RC0603FR-0710KL"))
      (libsource (lib "eagle-import") (part "RC0603FR-0710KL"))
    )
    (comp (ref "R39")
      (value "RC0603FR-0710KL")
      (footprint "eagle-import:RESC1608X55N")
      (fields (field (name "MOUSER_PART_NUMBER") "603-RC0603FR-0710KL"))
      (libsource (lib "eagle-import") (part "RC0603FR-0710KL"))
    )
    (comp (ref "R40")
      (value "RC0603FR-0710KL")
      (footprint "eagle-import:RESC1608X55N")
      (fields (field (name "MOUSER_PART_NUMBER") "603-RC0603FR-0710KL"))
      (libsource (lib "eagle-import") (part "RC0603FR-0710KL"))
    )
    (comp (ref "R41")
      (value "RC0603FR-0710KL")
      (footprint "eagle-import:RESC1608X55N")
      (fields (field (name "MOUSER_PART_NUMBER") "603-RC0603FR-0710KL"))
      (libsource (lib "eagle-import") (part "RC0603FR-0710KL"))
    )
    (comp (ref "R42")
      (value "RC0603FR-0710KL")
      (footprint "eagle-import:RESC1608X55N")
      (fields (field (name "MOUSER_PART_NUMBER") "603-RC0603FR-0710KL"))
      (libsource (lib "eagle-import") (part "RC0603FR-0710KL"))
    )
    (comp (ref "R43")
      (value "RC0603FR-0710KL")
      (footprint "eagle-import:RESC1608X55N")
      (fields (field (name "MOUSER_PART_NUMBER") "603-RC0603FR-0710KL"))
      (libsource (lib "eagle-import") (part "RC0603FR-0710KL"))
    )
    (comp (ref "R44")
      (value "RC0603FR-0710KL")
      (footprint "eagle-import:RESC1608X55N")
      (fields (field (name "MOUSER_PART_NUMBER") "603-RC0603FR-0710KL"))
      (libsource (lib "eagle-import") (part "RC0603FR-0710KL"))
    )
    (comp (ref "R45")
      (value "RC0603FR-0710KL")
      (footprint "eagle-import:RESC1608X55N")
      (fields (field (name "MOUSER_PART_NUMBER") "603-RC0603FR-0710KL"))
      (libsource (lib "eagle-import") (part "RC0603FR-0710KL"))
    )
    (comp (ref "R46")
      (value "RC0603FR-0710KL")
      (footprint "eagle-import:RESC1608X55N")
      (fields (field (name "MOUSER_PART_NUMBER") "603-RC0603FR-0710KL"))
      (libsource (lib "eagle-import") (part "RC0603FR-0710KL"))
    )
    (comp (ref "R47")
      (value "RC0603FR-0710KL")
      (footprint "eagle-import:RESC1608X55N")
      (fields (field (name "MOUSER_PART_NUMBER") "603-RC0603FR-0710KL"))
      (libsource (lib "eagle-import") (part "RC0603FR-0710KL"))
    )
    (comp (ref "R48")
      (value "RC0603FR-0710KL")
      (footprint "eagle-import:RESC1608X55N")
      (fields (field (name "MOUSER_PART_NUMBER") "603-RC0603FR-0710KL"))
      (libsource (lib "eagle-import") (part "RC0603FR-0710KL"))
    )
    (comp (ref "R49")
      (value "RC0603FR-0710KL")
      (footprint "eagle-import:RESC1608X55N")
      (fields (field (name "MOUSER_PART_NUMBER") "603-RC0603FR-0710KL"))
      (libsource (lib "eagle-import") (part "RC0603FR-0710KL"))
    )
    (comp (ref "R50")
      (value "RC0603FR-0710KL")
      (footprint "eagle-import:RESC1608X55N")
      (fields (field (name "MOUSER_PART_NUMBER") "603-RC0603FR-0710KL"))
      (libsource (lib "eagle-import") (part "RC0603FR-0710KL"))
    )
    (comp (ref "R51")
      (value "RC0603FR-0710KL")
      (footprint "eagle-import:RESC1608X55N")
      (fields (field (name "MOUSER_PART_NUMBER") "603-RC0603FR-0710KL"))
      (libsource (lib "eagle-import") (part "RC0603FR-0710KL"))
    )
    (comp (ref "R52")
      (value "RC0603FR-0710KL")
      (footprint "eagle-import:RESC1608X55N")
      (fields (field (name "MOUSER_PART_NUMBER") "603-RC0603FR-0710KL"))
      (libsource (lib "eagle-import") (part "RC0603FR-0710KL"))
    )
    (comp (ref "R53")
      (value "RC0603FR-0710KL")
      (footprint "eagle-import:RESC1608X55N")
      (fields (field (name "MOUSER_PART_NUMBER") "603-RC0603FR-0710KL"))
      (libsource (lib "eagle-import") (part "RC0603FR-0710KL"))
    )
    (comp (ref "R54")
      (value "RC0603FR-0710KL")
      (footprint "eagle-import:RESC1608X55N")
      (fields (field (name "MOUSER_PART_NUMBER") "603-RC0603FR-0710KL"))
      (libsource (lib "eagle-import") (part "RC0603FR-0710KL"))
    )
    (comp (ref "R55")
      (value "RC0603FR-0710KL")
      (footprint "eagle-import:RESC1608X55N")
      (fields (field (name "MOUSER_PART_NUMBER") "603-RC0603FR-0710KL"))
      (libsource (lib "eagle-import") (part "RC0603FR-0710KL"))
    )
    (comp (ref "R56")
      (value "RC0603FR-0710KL")
      (footprint "eagle-import:RESC1608X55N")
      (fields (field (name "MOUSER_PART_NUMBER") "603-RC0603FR-0710KL"))
      (libsource (lib "eagle-import") (part "RC0603FR-0710KL"))
    )
    (comp (ref "R57")
      (value "RC0603FR-0710KL")
      (footprint "eagle-import:RESC1608X55N")
      (fields (field (name "MOUSER_PART_NUMBER") "603-RC0603FR-0710KL"))
      (libsource (lib "eagle-import") (part "RC0603FR-0710KL"))
    )
    (comp (ref "R58")
      (value "RC0603FR-0710KL")
      (footprint "eagle-import:RESC1608X55N")
      (fields (field (name "MOUSER_PART_NUMBER") "603-RC0603FR-0710KL"))
      (libsource (lib "eagle-import") (part "RC0603FR-0710KL"))
    )
    (comp (ref "R59")
      (value "RC0603FR-0710KL")
      (footprint "eagle-import:RESC1608X55N")
      (fields (field (name "MOUSER_PART_NUMBER") "603-RC0603FR-0710KL"))
      (libsource (lib "eagle-import") (part "RC0603FR-0710KL"))
    )
    (comp (ref "R60")
      (value "RC0603FR-0710KL")
      (footprint "eagle-import:RESC1608X55N")
      (fields (field (name "MOUSER_PART_NUMBER") "603-RC0603FR-0710KL"))
      (libsource (lib "eagle-import") (part "RC0603FR-0710KL"))
    )
    (comp (ref "R61")
      (value "RC0603FR-0710KL")
      (footprint "eagle-import:RESC1608X55N")
      (fields (field (name "MOUSER_PART_NUMBER") "603-RC0603FR-0710KL"))
      (libsource (lib "eagle-import") (part "RC0603FR-0710KL"))
    )
    (comp (ref "R62")
      (value "RC0603FR-0710KL")
      (footprint "eagle-import:RESC1608X55N")
      (fields (field (name "MOUSER_PART_NUMBER") "603-RC0603FR-0710KL"))
      (libsource (lib "eagle-import") (part "RC0603FR-0710KL"))
    )
    (comp (ref "R63")
      (value "RC0603FR-0710KL")
      (footprint "eagle-import:RESC1608X55N")
      (fields (field (name "MOUSER_PART_NUMBER") "603-RC0603FR-0710KL"))
      (libsource (lib "eagle-import") (part "RC0603FR-0710KL"))
    )
    (comp (ref "R64")
      (value "RC0603FR-0710KL")
      (footprint "eagle-import:RESC1608X55N")
      (fields (field (name "MOUSER_PART_NUMBER") "603-RC0603FR-0710KL"))
      (libsource (lib "eagle-import") (part "RC0603FR-0710KL"))
    )
  )
  (nets
    (net (code "1") (name "/AND1_B1") (class "Default")
      (node (ref "IC33") (pin "3") (pinfunction "1Y_3") (pintype "bidirectional"))
      (node (ref "IC42") (pin "1") (pinfunction "1A_1") (pintype "bidirectional"))
    )
    (net (code "2") (name "/AND1_B2") (class "Default")
      (node (ref "IC33") (pin "6") (pinfunction "2Y_6") (pintype "bidirectional"))
      (node (ref "IC42") (pin "4") (pinfunction "2A_4") (pintype "bidirectional"))
    )
    (net (code "3") (name "/AND1_B3") (class "Default")
      (node (ref "IC33") (pin "11") (pinfunction "4Y_11") (pintype "bidirectional"))
      (node (ref "IC42") (pin "12") (pinfunction "4A_12") (pintype "bidirectional"))
    )
    (net (code "4") (name "/AND1_B4") (class "Default")
      (node (ref "IC33") (pin "8") (pinfunction "3Y_8") (pintype "bidirectional"))
      (node (ref "IC42") (pin "9") (pinfunction "3A_9") (pintype "bidirectional"))
    )
    (net (code "5") (name "/AND1_B5") (class "Default")
      (node (ref "IC35") (pin "3") (pinfunction "1Y_3") (pintype "bidirectional"))
      (node (ref "IC44") (pin "1") (pinfunction "1A_1") (pintype "bidirectional"))
    )
    (net (code "6") (name "/AND1_B6") (class "Default")
      (node (ref "IC35") (pin "6") (pinfunction "2Y_6") (pintype "bidirectional"))
      (node (ref "IC44") (pin "4") (pinfunction "2A_4") (pintype "bidirectional"))
    )
    (net (code "7") (name "/AND1_B7") (class "Default")
      (node (ref "IC35") (pin "11") (pinfunction "4Y_11") (pintype "bidirectional"))
      (node (ref "IC44") (pin "12") (pinfunction "4A_12") (pintype "bidirectional"))
    )
    (net (code "8") (name "/AND1_B8") (class "Default")
      (node (ref "IC35") (pin "8") (pinfunction "3Y_8") (pintype "bidirectional"))
      (node (ref "IC44") (pin "9") (pinfunction "3A_9") (pintype "bidirectional"))
    )
    (net (code "9") (name "/AND1_B9") (class "Default")
      (node (ref "IC37") (pin "3") (pinfunction "1Y_3") (pintype "bidirectional"))
      (node (ref "IC46") (pin "1") (pinfunction "1A_1") (pintype "bidirectional"))
    )
    (net (code "10") (name "/AND1_B10") (class "Default")
      (node (ref "IC37") (pin "6") (pinfunction "2Y_6") (pintype "bidirectional"))
      (node (ref "IC46") (pin "4") (pinfunction "2A_4") (pintype "bidirectional"))
    )
    (net (code "11") (name "/AND1_B11") (class "Default")
      (node (ref "IC37") (pin "11") (pinfunction "4Y_11") (pintype "bidirectional"))
      (node (ref "IC46") (pin "12") (pinfunction "4A_12") (pintype "bidirectional"))
    )
    (net (code "12") (name "/AND1_B12") (class "Default")
      (node (ref "IC37") (pin "8") (pinfunction "3Y_8") (pintype "bidirectional"))
      (node (ref "IC46") (pin "9") (pinfunction "3A_9") (pintype "bidirectional"))
    )
    (net (code "13") (name "/AND1_B13") (class "Default")
      (node (ref "IC39") (pin "3") (pinfunction "1Y_3") (pintype "bidirectional"))
      (node (ref "IC48") (pin "1") (pinfunction "1A_1") (pintype "bidirectional"))
    )
    (net (code "14") (name "/AND1_B14") (class "Default")
      (node (ref "IC39") (pin "6") (pinfunction "2Y_6") (pintype "bidirectional"))
      (node (ref "IC48") (pin "4") (pinfunction "2A_4") (pintype "bidirectional"))
    )
    (net (code "15") (name "/AND1_B15") (class "Default")
      (node (ref "IC39") (pin "11") (pinfunction "4Y_11") (pintype "bidirectional"))
      (node (ref "IC48") (pin "12") (pinfunction "4A_12") (pintype "bidirectional"))
    )
    (net (code "16") (name "/AND1_B16") (class "Default")
      (node (ref "IC39") (pin "8") (pinfunction "3Y_8") (pintype "bidirectional"))
      (node (ref "IC48") (pin "9") (pinfunction "3A_9") (pintype "bidirectional"))
    )
    (net (code "17") (name "/AND1_B17") (class "Default")
      (node (ref "IC34") (pin "3") (pinfunction "1Y_3") (pintype "bidirectional"))
      (node (ref "IC41") (pin "1") (pinfunction "1A_1") (pintype "bidirectional"))
    )
    (net (code "18") (name "/AND1_B18") (class "Default")
      (node (ref "IC34") (pin "6") (pinfunction "2Y_6") (pintype "bidirectional"))
      (node (ref "IC41") (pin "4") (pinfunction "2A_4") (pintype "bidirectional"))
    )
    (net (code "19") (name "/AND1_B19") (class "Default")
      (node (ref "IC34") (pin "11") (pinfunction "4Y_11") (pintype "bidirectional"))
      (node (ref "IC41") (pin "12") (pinfunction "4A_12") (pintype "bidirectional"))
    )
    (net (code "20") (name "/AND1_B20") (class "Default")
      (node (ref "IC34") (pin "8") (pinfunction "3Y_8") (pintype "bidirectional"))
      (node (ref "IC41") (pin "9") (pinfunction "3A_9") (pintype "bidirectional"))
    )
    (net (code "21") (name "/AND1_B21") (class "Default")
      (node (ref "IC36") (pin "3") (pinfunction "1Y_3") (pintype "bidirectional"))
      (node (ref "IC43") (pin "1") (pinfunction "1A_1") (pintype "bidirectional"))
    )
    (net (code "22") (name "/AND1_B22") (class "Default")
      (node (ref "IC36") (pin "6") (pinfunction "2Y_6") (pintype "bidirectional"))
      (node (ref "IC43") (pin "4") (pinfunction "2A_4") (pintype "bidirectional"))
    )
    (net (code "23") (name "/AND1_B23") (class "Default")
      (node (ref "IC36") (pin "11") (pinfunction "4Y_11") (pintype "bidirectional"))
      (node (ref "IC43") (pin "12") (pinfunction "4A_12") (pintype "bidirectional"))
    )
    (net (code "24") (name "/AND1_B24") (class "Default")
      (node (ref "IC36") (pin "8") (pinfunction "3Y_8") (pintype "bidirectional"))
      (node (ref "IC43") (pin "9") (pinfunction "3A_9") (pintype "bidirectional"))
    )
    (net (code "25") (name "/AND1_B25") (class "Default")
      (node (ref "IC38") (pin "3") (pinfunction "1Y_3") (pintype "bidirectional"))
      (node (ref "IC45") (pin "1") (pinfunction "1A_1") (pintype "bidirectional"))
    )
    (net (code "26") (name "/AND1_B26") (class "Default")
      (node (ref "IC38") (pin "6") (pinfunction "2Y_6") (pintype "bidirectional"))
      (node (ref "IC45") (pin "4") (pinfunction "2A_4") (pintype "bidirectional"))
    )
    (net (code "27") (name "/AND1_B27") (class "Default")
      (node (ref "IC38") (pin "11") (pinfunction "4Y_11") (pintype "bidirectional"))
      (node (ref "IC45") (pin "12") (pinfunction "4A_12") (pintype "bidirectional"))
    )
    (net (code "28") (name "/AND1_B28") (class "Default")
      (node (ref "IC38") (pin "8") (pinfunction "3Y_8") (pintype "bidirectional"))
      (node (ref "IC45") (pin "9") (pinfunction "3A_9") (pintype "bidirectional"))
    )
    (net (code "29") (name "/AND1_B29") (class "Default")
      (node (ref "IC40") (pin "3") (pinfunction "1Y_3") (pintype "bidirectional"))
      (node (ref "IC47") (pin "1") (pinfunction "1A_1") (pintype "bidirectional"))
    )
    (net (code "30") (name "/AND1_B30") (class "Default")
      (node (ref "IC40") (pin "6") (pinfunction "2Y_6") (pintype "bidirectional"))
      (node (ref "IC47") (pin "4") (pinfunction "2A_4") (pintype "bidirectional"))
    )
    (net (code "31") (name "/AND1_B31") (class "Default")
      (node (ref "IC40") (pin "11") (pinfunction "4Y_11") (pintype "bidirectional"))
      (node (ref "IC47") (pin "12") (pinfunction "4A_12") (pintype "bidirectional"))
    )
    (net (code "32") (name "/AND1_B32") (class "Default")
      (node (ref "IC40") (pin "8") (pinfunction "3Y_8") (pintype "bidirectional"))
      (node (ref "IC47") (pin "9") (pinfunction "3A_9") (pintype "bidirectional"))
    )
    (net (code "33") (name "/AND2_B1") (class "Default")
      (node (ref "IC25") (pin "3") (pinfunction "1Y_3") (pintype "bidirectional"))
      (node (ref "IC42") (pin "2") (pinfunction "1B_2") (pintype "bidirectional"))
    )
    (net (code "34") (name "/AND2_B2") (class "Default")
      (node (ref "IC25") (pin "6") (pinfunction "2Y_6") (pintype "bidirectional"))
      (node (ref "IC42") (pin "5") (pinfunction "2B_5") (pintype "bidirectional"))
    )
    (net (code "35") (name "/AND2_B3") (class "Default")
      (node (ref "IC25") (pin "11") (pinfunction "4Y_11") (pintype "bidirectional"))
      (node (ref "IC42") (pin "13") (pinfunction "4B_13") (pintype "bidirectional"))
    )
    (net (code "36") (name "/AND2_B4") (class "Default")
      (node (ref "IC25") (pin "8") (pinfunction "3Y_8") (pintype "bidirectional"))
      (node (ref "IC42") (pin "10") (pinfunction "3B_10") (pintype "bidirectional"))
    )
    (net (code "37") (name "/AND2_B5") (class "Default")
      (node (ref "IC27") (pin "3") (pinfunction "1Y_3") (pintype "bidirectional"))
      (node (ref "IC44") (pin "2") (pinfunction "1B_2") (pintype "bidirectional"))
    )
    (net (code "38") (name "/AND2_B6") (class "Default")
      (node (ref "IC27") (pin "6") (pinfunction "2Y_6") (pintype "bidirectional"))
      (node (ref "IC44") (pin "5") (pinfunction "2B_5") (pintype "bidirectional"))
    )
    (net (code "39") (name "/AND2_B7") (class "Default")
      (node (ref "IC27") (pin "11") (pinfunction "4Y_11") (pintype "bidirectional"))
      (node (ref "IC44") (pin "13") (pinfunction "4B_13") (pintype "bidirectional"))
    )
    (net (code "40") (name "/AND2_B8") (class "Default")
      (node (ref "IC27") (pin "8") (pinfunction "3Y_8") (pintype "bidirectional"))
      (node (ref "IC44") (pin "10") (pinfunction "3B_10") (pintype "bidirectional"))
    )
    (net (code "41") (name "/AND2_B9") (class "Default")
      (node (ref "IC29") (pin "3") (pinfunction "1Y_3") (pintype "bidirectional"))
      (node (ref "IC46") (pin "2") (pinfunction "1B_2") (pintype "bidirectional"))
    )
    (net (code "42") (name "/AND2_B10") (class "Default")
      (node (ref "IC29") (pin "6") (pinfunction "2Y_6") (pintype "bidirectional"))
      (node (ref "IC46") (pin "5") (pinfunction "2B_5") (pintype "bidirectional"))
    )
    (net (code "43") (name "/AND2_B11") (class "Default")
      (node (ref "IC29") (pin "11") (pinfunction "4Y_11") (pintype "bidirectional"))
      (node (ref "IC46") (pin "13") (pinfunction "4B_13") (pintype "bidirectional"))
    )
    (net (code "44") (name "/AND2_B12") (class "Default")
      (node (ref "IC29") (pin "8") (pinfunction "3Y_8") (pintype "bidirectional"))
      (node (ref "IC46") (pin "10") (pinfunction "3B_10") (pintype "bidirectional"))
    )
    (net (code "45") (name "/AND2_B13") (class "Default")
      (node (ref "IC31") (pin "3") (pinfunction "1Y_3") (pintype "bidirectional"))
      (node (ref "IC48") (pin "2") (pinfunction "1B_2") (pintype "bidirectional"))
    )
    (net (code "46") (name "/AND2_B14") (class "Default")
      (node (ref "IC31") (pin "6") (pinfunction "2Y_6") (pintype "bidirectional"))
      (node (ref "IC48") (pin "5") (pinfunction "2B_5") (pintype "bidirectional"))
    )
    (net (code "47") (name "/AND2_B15") (class "Default")
      (node (ref "IC31") (pin "11") (pinfunction "4Y_11") (pintype "bidirectional"))
      (node (ref "IC48") (pin "13") (pinfunction "4B_13") (pintype "bidirectional"))
    )
    (net (code "48") (name "/AND2_B16") (class "Default")
      (node (ref "IC31") (pin "8") (pinfunction "3Y_8") (pintype "bidirectional"))
      (node (ref "IC48") (pin "10") (pinfunction "3B_10") (pintype "bidirectional"))
    )
    (net (code "49") (name "/AND2_B17") (class "Default")
      (node (ref "IC26") (pin "3") (pinfunction "1Y_3") (pintype "bidirectional"))
      (node (ref "IC41") (pin "2") (pinfunction "1B_2") (pintype "bidirectional"))
    )
    (net (code "50") (name "/AND2_B18") (class "Default")
      (node (ref "IC26") (pin "6") (pinfunction "2Y_6") (pintype "bidirectional"))
      (node (ref "IC41") (pin "5") (pinfunction "2B_5") (pintype "bidirectional"))
    )
    (net (code "51") (name "/AND2_B19") (class "Default")
      (node (ref "IC26") (pin "11") (pinfunction "4Y_11") (pintype "bidirectional"))
      (node (ref "IC41") (pin "13") (pinfunction "4B_13") (pintype "bidirectional"))
    )
    (net (code "52") (name "/AND2_B20") (class "Default")
      (node (ref "IC26") (pin "8") (pinfunction "3Y_8") (pintype "bidirectional"))
      (node (ref "IC41") (pin "10") (pinfunction "3B_10") (pintype "bidirectional"))
    )
    (net (code "53") (name "/AND2_B21") (class "Default")
      (node (ref "IC28") (pin "3") (pinfunction "1Y_3") (pintype "bidirectional"))
      (node (ref "IC43") (pin "2") (pinfunction "1B_2") (pintype "bidirectional"))
    )
    (net (code "54") (name "/AND2_B22") (class "Default")
      (node (ref "IC28") (pin "6") (pinfunction "2Y_6") (pintype "bidirectional"))
      (node (ref "IC43") (pin "5") (pinfunction "2B_5") (pintype "bidirectional"))
    )
    (net (code "55") (name "/AND2_B23") (class "Default")
      (node (ref "IC28") (pin "11") (pinfunction "4Y_11") (pintype "bidirectional"))
      (node (ref "IC43") (pin "13") (pinfunction "4B_13") (pintype "bidirectional"))
    )
    (net (code "56") (name "/AND2_B24") (class "Default")
      (node (ref "IC28") (pin "8") (pinfunction "3Y_8") (pintype "bidirectional"))
      (node (ref "IC43") (pin "10") (pinfunction "3B_10") (pintype "bidirectional"))
    )
    (net (code "57") (name "/AND2_B25") (class "Default")
      (node (ref "IC30") (pin "3") (pinfunction "1Y_3") (pintype "bidirectional"))
      (node (ref "IC45") (pin "2") (pinfunction "1B_2") (pintype "bidirectional"))
    )
    (net (code "58") (name "/AND2_B26") (class "Default")
      (node (ref "IC30") (pin "6") (pinfunction "2Y_6") (pintype "bidirectional"))
      (node (ref "IC45") (pin "5") (pinfunction "2B_5") (pintype "bidirectional"))
    )
    (net (code "59") (name "/AND2_B27") (class "Default")
      (node (ref "IC30") (pin "11") (pinfunction "4Y_11") (pintype "bidirectional"))
      (node (ref "IC45") (pin "13") (pinfunction "4B_13") (pintype "bidirectional"))
    )
    (net (code "60") (name "/AND2_B28") (class "Default")
      (node (ref "IC30") (pin "8") (pinfunction "3Y_8") (pintype "bidirectional"))
      (node (ref "IC45") (pin "10") (pinfunction "3B_10") (pintype "bidirectional"))
    )
    (net (code "61") (name "/AND2_B29") (class "Default")
      (node (ref "IC32") (pin "3") (pinfunction "1Y_3") (pintype "bidirectional"))
      (node (ref "IC47") (pin "2") (pinfunction "1B_2") (pintype "bidirectional"))
    )
    (net (code "62") (name "/AND2_B30") (class "Default")
      (node (ref "IC32") (pin "6") (pinfunction "2Y_6") (pintype "bidirectional"))
      (node (ref "IC47") (pin "5") (pinfunction "2B_5") (pintype "bidirectional"))
    )
    (net (code "63") (name "/AND2_B31") (class "Default")
      (node (ref "IC32") (pin "11") (pinfunction "4Y_11") (pintype "bidirectional"))
      (node (ref "IC47") (pin "13") (pinfunction "4B_13") (pintype "bidirectional"))
    )
    (net (code "64") (name "/AND2_B32") (class "Default")
      (node (ref "IC32") (pin "8") (pinfunction "3Y_8") (pintype "bidirectional"))
      (node (ref "IC47") (pin "10") (pinfunction "3B_10") (pintype "bidirectional"))
    )
    (net (code "65") (name "/CIN1") (class "Default")
      (node (ref "IC25") (pin "5") (pinfunction "2B_5") (pintype "bidirectional"))
      (node (ref "IC42") (pin "3") (pinfunction "1Y_3") (pintype "bidirectional"))
      (node (ref "IC9") (pin "5") (pinfunction "2B_5") (pintype "bidirectional"))
    )
    (net (code "66") (name "/CIN2") (class "Default")
      (node (ref "IC25") (pin "12") (pinfunction "4A_12") (pintype "bidirectional"))
      (node (ref "IC42") (pin "6") (pinfunction "2Y_6") (pintype "bidirectional"))
      (node (ref "IC9") (pin "13") (pinfunction "4B_13") (pintype "bidirectional"))
    )
    (net (code "67") (name "/CIN3") (class "Default")
      (node (ref "IC25") (pin "9") (pinfunction "3A_9") (pintype "bidirectional"))
      (node (ref "IC42") (pin "11") (pinfunction "4Y_11") (pintype "bidirectional"))
      (node (ref "IC9") (pin "10") (pinfunction "3B_10") (pintype "bidirectional"))
    )
    (net (code "68") (name "/CIN4") (class "Default")
      (node (ref "IC11") (pin "2") (pinfunction "1B_2") (pintype "bidirectional"))
      (node (ref "IC27") (pin "2") (pinfunction "1B_2") (pintype "bidirectional"))
      (node (ref "IC42") (pin "8") (pinfunction "3Y_8") (pintype "bidirectional"))
    )
    (net (code "69") (name "/CIN5") (class "Default")
      (node (ref "IC11") (pin "5") (pinfunction "2B_5") (pintype "bidirectional"))
      (node (ref "IC27") (pin "5") (pinfunction "2B_5") (pintype "bidirectional"))
      (node (ref "IC44") (pin "3") (pinfunction "1Y_3") (pintype "bidirectional"))
    )
    (net (code "70") (name "/CIN6") (class "Default")
      (node (ref "IC11") (pin "13") (pinfunction "4B_13") (pintype "bidirectional"))
      (node (ref "IC27") (pin "12") (pinfunction "4A_12") (pintype "bidirectional"))
      (node (ref "IC44") (pin "6") (pinfunction "2Y_6") (pintype "bidirectional"))
    )
    (net (code "71") (name "/CIN7") (class "Default")
      (node (ref "IC11") (pin "10") (pinfunction "3B_10") (pintype "bidirectional"))
      (node (ref "IC27") (pin "9") (pinfunction "3A_9") (pintype "bidirectional"))
      (node (ref "IC44") (pin "11") (pinfunction "4Y_11") (pintype "bidirectional"))
    )
    (net (code "72") (name "/CIN8") (class "Default")
      (node (ref "IC13") (pin "2") (pinfunction "1B_2") (pintype "bidirectional"))
      (node (ref "IC29") (pin "2") (pinfunction "1B_2") (pintype "bidirectional"))
      (node (ref "IC44") (pin "8") (pinfunction "3Y_8") (pintype "bidirectional"))
    )
    (net (code "73") (name "/CIN9") (class "Default")
      (node (ref "IC13") (pin "5") (pinfunction "2B_5") (pintype "bidirectional"))
      (node (ref "IC29") (pin "5") (pinfunction "2B_5") (pintype "bidirectional"))
      (node (ref "IC46") (pin "3") (pinfunction "1Y_3") (pintype "bidirectional"))
    )
    (net (code "74") (name "/CIN10") (class "Default")
      (node (ref "IC13") (pin "13") (pinfunction "4B_13") (pintype "bidirectional"))
      (node (ref "IC29") (pin "12") (pinfunction "4A_12") (pintype "bidirectional"))
      (node (ref "IC46") (pin "6") (pinfunction "2Y_6") (pintype "bidirectional"))
    )
    (net (code "75") (name "/CIN11") (class "Default")
      (node (ref "IC13") (pin "10") (pinfunction "3B_10") (pintype "bidirectional"))
      (node (ref "IC29") (pin "9") (pinfunction "3A_9") (pintype "bidirectional"))
      (node (ref "IC46") (pin "11") (pinfunction "4Y_11") (pintype "bidirectional"))
    )
    (net (code "76") (name "/CIN12") (class "Default")
      (node (ref "IC15") (pin "2") (pinfunction "1B_2") (pintype "bidirectional"))
      (node (ref "IC31") (pin "2") (pinfunction "1B_2") (pintype "bidirectional"))
      (node (ref "IC46") (pin "8") (pinfunction "3Y_8") (pintype "bidirectional"))
    )
    (net (code "77") (name "/CIN13") (class "Default")
      (node (ref "IC15") (pin "5") (pinfunction "2B_5") (pintype "bidirectional"))
      (node (ref "IC31") (pin "5") (pinfunction "2B_5") (pintype "bidirectional"))
      (node (ref "IC48") (pin "3") (pinfunction "1Y_3") (pintype "bidirectional"))
    )
    (net (code "78") (name "/CIN14") (class "Default")
      (node (ref "IC15") (pin "13") (pinfunction "4B_13") (pintype "bidirectional"))
      (node (ref "IC31") (pin "12") (pinfunction "4A_12") (pintype "bidirectional"))
      (node (ref "IC48") (pin "6") (pinfunction "2Y_6") (pintype "bidirectional"))
    )
    (net (code "79") (name "/CIN15") (class "Default")
      (node (ref "IC15") (pin "10") (pinfunction "3B_10") (pintype "bidirectional"))
      (node (ref "IC31") (pin "9") (pinfunction "3A_9") (pintype "bidirectional"))
      (node (ref "IC48") (pin "11") (pinfunction "4Y_11") (pintype "bidirectional"))
    )
    (net (code "80") (name "/CIN16") (class "Default")
      (node (ref "IC10") (pin "2") (pinfunction "1B_2") (pintype "bidirectional"))
      (node (ref "IC26") (pin "2") (pinfunction "1B_2") (pintype "bidirectional"))
      (node (ref "IC48") (pin "8") (pinfunction "3Y_8") (pintype "bidirectional"))
    )
    (net (code "81") (name "/CIN17") (class "Default")
      (node (ref "IC10") (pin "5") (pinfunction "2B_5") (pintype "bidirectional"))
      (node (ref "IC26") (pin "5") (pinfunction "2B_5") (pintype "bidirectional"))
      (node (ref "IC41") (pin "3") (pinfunction "1Y_3") (pintype "bidirectional"))
    )
    (net (code "82") (name "/CIN18") (class "Default")
      (node (ref "IC10") (pin "13") (pinfunction "4B_13") (pintype "bidirectional"))
      (node (ref "IC26") (pin "12") (pinfunction "4A_12") (pintype "bidirectional"))
      (node (ref "IC41") (pin "6") (pinfunction "2Y_6") (pintype "bidirectional"))
    )
    (net (code "83") (name "/CIN19") (class "Default")
      (node (ref "IC10") (pin "10") (pinfunction "3B_10") (pintype "bidirectional"))
      (node (ref "IC26") (pin "9") (pinfunction "3A_9") (pintype "bidirectional"))
      (node (ref "IC41") (pin "11") (pinfunction "4Y_11") (pintype "bidirectional"))
    )
    (net (code "84") (name "/CIN20") (class "Default")
      (node (ref "IC12") (pin "2") (pinfunction "1B_2") (pintype "bidirectional"))
      (node (ref "IC28") (pin "2") (pinfunction "1B_2") (pintype "bidirectional"))
      (node (ref "IC41") (pin "8") (pinfunction "3Y_8") (pintype "bidirectional"))
    )
    (net (code "85") (name "/CIN21") (class "Default")
      (node (ref "IC12") (pin "5") (pinfunction "2B_5") (pintype "bidirectional"))
      (node (ref "IC28") (pin "5") (pinfunction "2B_5") (pintype "bidirectional"))
      (node (ref "IC43") (pin "3") (pinfunction "1Y_3") (pintype "bidirectional"))
    )
    (net (code "86") (name "/CIN22") (class "Default")
      (node (ref "IC12") (pin "13") (pinfunction "4B_13") (pintype "bidirectional"))
      (node (ref "IC28") (pin "12") (pinfunction "4A_12") (pintype "bidirectional"))
      (node (ref "IC43") (pin "6") (pinfunction "2Y_6") (pintype "bidirectional"))
    )
    (net (code "87") (name "/CIN23") (class "Default")
      (node (ref "IC12") (pin "10") (pinfunction "3B_10") (pintype "bidirectional"))
      (node (ref "IC28") (pin "9") (pinfunction "3A_9") (pintype "bidirectional"))
      (node (ref "IC43") (pin "11") (pinfunction "4Y_11") (pintype "bidirectional"))
    )
    (net (code "88") (name "/CIN24") (class "Default")
      (node (ref "IC14") (pin "2") (pinfunction "1B_2") (pintype "bidirectional"))
      (node (ref "IC30") (pin "2") (pinfunction "1B_2") (pintype "bidirectional"))
      (node (ref "IC43") (pin "8") (pinfunction "3Y_8") (pintype "bidirectional"))
    )
    (net (code "89") (name "/CIN25") (class "Default")
      (node (ref "IC14") (pin "5") (pinfunction "2B_5") (pintype "bidirectional"))
      (node (ref "IC30") (pin "5") (pinfunction "2B_5") (pintype "bidirectional"))
      (node (ref "IC45") (pin "3") (pinfunction "1Y_3") (pintype "bidirectional"))
    )
    (net (code "90") (name "/CIN26") (class "Default")
      (node (ref "IC14") (pin "13") (pinfunction "4B_13") (pintype "bidirectional"))
      (node (ref "IC30") (pin "12") (pinfunction "4A_12") (pintype "bidirectional"))
      (node (ref "IC45") (pin "6") (pinfunction "2Y_6") (pintype "bidirectional"))
    )
    (net (code "91") (name "/CIN27") (class "Default")
      (node (ref "IC14") (pin "10") (pinfunction "3B_10") (pintype "bidirectional"))
      (node (ref "IC30") (pin "9") (pinfunction "3A_9") (pintype "bidirectional"))
      (node (ref "IC45") (pin "11") (pinfunction "4Y_11") (pintype "bidirectional"))
    )
    (net (code "92") (name "/CIN28") (class "Default")
      (node (ref "IC16") (pin "2") (pinfunction "1B_2") (pintype "bidirectional"))
      (node (ref "IC32") (pin "2") (pinfunction "1B_2") (pintype "bidirectional"))
      (node (ref "IC45") (pin "8") (pinfunction "3Y_8") (pintype "bidirectional"))
    )
    (net (code "93") (name "/CIN29") (class "Default")
      (node (ref "IC16") (pin "5") (pinfunction "2B_5") (pintype "bidirectional"))
      (node (ref "IC32") (pin "5") (pinfunction "2B_5") (pintype "bidirectional"))
      (node (ref "IC47") (pin "3") (pinfunction "1Y_3") (pintype "bidirectional"))
    )
    (net (code "94") (name "/CIN30") (class "Default")
      (node (ref "IC16") (pin "13") (pinfunction "4B_13") (pintype "bidirectional"))
      (node (ref "IC32") (pin "12") (pinfunction "4A_12") (pintype "bidirectional"))
      (node (ref "IC47") (pin "6") (pinfunction "2Y_6") (pintype "bidirectional"))
    )
    (net (code "95") (name "/CIN31") (class "Default")
      (node (ref "IC16") (pin "10") (pinfunction "3B_10") (pintype "bidirectional"))
      (node (ref "IC32") (pin "9") (pinfunction "3A_9") (pintype "bidirectional"))
      (node (ref "IC47") (pin "11") (pinfunction "4Y_11") (pintype "bidirectional"))
    )
    (net (code "96") (name "/CIN32") (class "Default")
      (node (ref "IC47") (pin "8") (pinfunction "3Y_8") (pintype "bidirectional"))
    )
    (net (code "97") (name "/D1_B1") (class "Default")
      (node (ref "IC1") (pin "1") (pinfunction "1A_1") (pintype "bidirectional"))
      (node (ref "IC33") (pin "1") (pinfunction "1A_1") (pintype "bidirectional"))
      (node (ref "JP2") (pin "5") (pinfunction "5_5") (pintype "passive"))
      (node (ref "JP3") (pin "5") (pinfunction "5_5") (pintype "passive"))
      (node (ref "R1") (pin "1") (pinfunction "1_1") (pintype "bidirectional"))
    )
    (net (code "98") (name "/D1_B2") (class "Default")
      (node (ref "IC1") (pin "4") (pinfunction "2A_4") (pintype "bidirectional"))
      (node (ref "IC33") (pin "4") (pinfunction "2A_4") (pintype "bidirectional"))
      (node (ref "JP2") (pin "7") (pinfunction "7_7") (pintype "passive"))
      (node (ref "JP3") (pin "7") (pinfunction "7_7") (pintype "passive"))
      (node (ref "R2") (pin "1") (pinfunction "1_1") (pintype "bidirectional"))
    )
    (net (code "99") (name "/D1_B3") (class "Default")
      (node (ref "IC1") (pin "12") (pinfunction "4A_12") (pintype "bidirectional"))
      (node (ref "IC33") (pin "13") (pinfunction "4B_13") (pintype "bidirectional"))
      (node (ref "JP2") (pin "9") (pinfunction "9_9") (pintype "passive"))
      (node (ref "JP3") (pin "9") (pinfunction "9_9") (pintype "passive"))
      (node (ref "R3") (pin "1") (pinfunction "1_1") (pintype "bidirectional"))
    )
    (net (code "100") (name "/D1_B4") (class "Default")
      (node (ref "IC1") (pin "9") (pinfunction "3A_9") (pintype "bidirectional"))
      (node (ref "IC33") (pin "10") (pinfunction "3B_10") (pintype "bidirectional"))
      (node (ref "JP2") (pin "11") (pinfunction "11_11") (pintype "passive"))
      (node (ref "JP3") (pin "11") (pinfunction "11_11") (pintype "passive"))
      (node (ref "R4") (pin "1") (pinfunction "1_1") (pintype "bidirectional"))
    )
    (net (code "101") (name "/D1_B5") (class "Default")
      (node (ref "IC3") (pin "1") (pinfunction "1A_1") (pintype "bidirectional"))
      (node (ref "IC35") (pin "1") (pinfunction "1A_1") (pintype "bidirectional"))
      (node (ref "JP2") (pin "13") (pinfunction "13_13") (pintype "passive"))
      (node (ref "JP3") (pin "13") (pinfunction "13_13") (pintype "passive"))
      (node (ref "R5") (pin "1") (pinfunction "1_1") (pintype "bidirectional"))
    )
    (net (code "102") (name "/D1_B6") (class "Default")
      (node (ref "IC3") (pin "4") (pinfunction "2A_4") (pintype "bidirectional"))
      (node (ref "IC35") (pin "4") (pinfunction "2A_4") (pintype "bidirectional"))
      (node (ref "JP2") (pin "15") (pinfunction "15_15") (pintype "passive"))
      (node (ref "JP3") (pin "15") (pinfunction "15_15") (pintype "passive"))
      (node (ref "R6") (pin "1") (pinfunction "1_1") (pintype "bidirectional"))
    )
    (net (code "103") (name "/D1_B7") (class "Default")
      (node (ref "IC3") (pin "12") (pinfunction "4A_12") (pintype "bidirectional"))
      (node (ref "IC35") (pin "13") (pinfunction "4B_13") (pintype "bidirectional"))
      (node (ref "JP2") (pin "17") (pinfunction "17_17") (pintype "passive"))
      (node (ref "JP3") (pin "17") (pinfunction "17_17") (pintype "passive"))
      (node (ref "R7") (pin "1") (pinfunction "1_1") (pintype "bidirectional"))
    )
    (net (code "104") (name "/D1_B8") (class "Default")
      (node (ref "IC3") (pin "9") (pinfunction "3A_9") (pintype "bidirectional"))
      (node (ref "IC35") (pin "10") (pinfunction "3B_10") (pintype "bidirectional"))
      (node (ref "JP2") (pin "19") (pinfunction "19_19") (pintype "passive"))
      (node (ref "JP3") (pin "19") (pinfunction "19_19") (pintype "passive"))
      (node (ref "R8") (pin "1") (pinfunction "1_1") (pintype "bidirectional"))
    )
    (net (code "105") (name "/D1_B9") (class "Default")
      (node (ref "IC37") (pin "1") (pinfunction "1A_1") (pintype "bidirectional"))
      (node (ref "IC5") (pin "1") (pinfunction "1A_1") (pintype "bidirectional"))
      (node (ref "JP2") (pin "21") (pinfunction "21_21") (pintype "passive"))
      (node (ref "JP3") (pin "21") (pinfunction "21_21") (pintype "passive"))
      (node (ref "R9") (pin "1") (pinfunction "1_1") (pintype "bidirectional"))
    )
    (net (code "106") (name "/D1_B10") (class "Default")
      (node (ref "IC37") (pin "4") (pinfunction "2A_4") (pintype "bidirectional"))
      (node (ref "IC5") (pin "4") (pinfunction "2A_4") (pintype "bidirectional"))
      (node (ref "JP2") (pin "23") (pinfunction "23_23") (pintype "passive"))
      (node (ref "JP3") (pin "23") (pinfunction "23_23") (pintype "passive"))
      (node (ref "R10") (pin "1") (pinfunction "1_1") (pintype "bidirectional"))
    )
    (net (code "107") (name "/D1_B11") (class "Default")
      (node (ref "IC37") (pin "13") (pinfunction "4B_13") (pintype "bidirectional"))
      (node (ref "IC5") (pin "12") (pinfunction "4A_12") (pintype "bidirectional"))
      (node (ref "JP2") (pin "25") (pinfunction "25_25") (pintype "passive"))
      (node (ref "JP3") (pin "25") (pinfunction "25_25") (pintype "passive"))
      (node (ref "R11") (pin "1") (pinfunction "1_1") (pintype "bidirectional"))
    )
    (net (code "108") (name "/D1_B12") (class "Default")
      (node (ref "IC37") (pin "10") (pinfunction "3B_10") (pintype "bidirectional"))
      (node (ref "IC5") (pin "9") (pinfunction "3A_9") (pintype "bidirectional"))
      (node (ref "JP2") (pin "27") (pinfunction "27_27") (pintype "passive"))
      (node (ref "JP3") (pin "27") (pinfunction "27_27") (pintype "passive"))
      (node (ref "R12") (pin "1") (pinfunction "1_1") (pintype "bidirectional"))
    )
    (net (code "109") (name "/D1_B13") (class "Default")
      (node (ref "IC39") (pin "1") (pinfunction "1A_1") (pintype "bidirectional"))
      (node (ref "IC7") (pin "1") (pinfunction "1A_1") (pintype "bidirectional"))
      (node (ref "JP2") (pin "29") (pinfunction "29_29") (pintype "passive"))
      (node (ref "JP3") (pin "29") (pinfunction "29_29") (pintype "passive"))
      (node (ref "R13") (pin "1") (pinfunction "1_1") (pintype "bidirectional"))
    )
    (net (code "110") (name "/D1_B14") (class "Default")
      (node (ref "IC39") (pin "4") (pinfunction "2A_4") (pintype "bidirectional"))
      (node (ref "IC7") (pin "4") (pinfunction "2A_4") (pintype "bidirectional"))
      (node (ref "JP2") (pin "31") (pinfunction "31_31") (pintype "passive"))
      (node (ref "JP3") (pin "31") (pinfunction "31_31") (pintype "passive"))
      (node (ref "R14") (pin "1") (pinfunction "1_1") (pintype "bidirectional"))
    )
    (net (code "111") (name "/D1_B15") (class "Default")
      (node (ref "IC39") (pin "13") (pinfunction "4B_13") (pintype "bidirectional"))
      (node (ref "IC7") (pin "12") (pinfunction "4A_12") (pintype "bidirectional"))
      (node (ref "JP2") (pin "33") (pinfunction "33_33") (pintype "passive"))
      (node (ref "JP3") (pin "33") (pinfunction "33_33") (pintype "passive"))
      (node (ref "R15") (pin "1") (pinfunction "1_1") (pintype "bidirectional"))
    )
    (net (code "112") (name "/D1_B16") (class "Default")
      (node (ref "IC39") (pin "10") (pinfunction "3B_10") (pintype "bidirectional"))
      (node (ref "IC7") (pin "9") (pinfunction "3A_9") (pintype "bidirectional"))
      (node (ref "JP2") (pin "35") (pinfunction "35_35") (pintype "passive"))
      (node (ref "JP3") (pin "35") (pinfunction "35_35") (pintype "passive"))
      (node (ref "R17") (pin "1") (pinfunction "1_1") (pintype "bidirectional"))
    )
    (net (code "113") (name "/D1_B17") (class "Default")
      (node (ref "IC2") (pin "1") (pinfunction "1A_1") (pintype "bidirectional"))
      (node (ref "IC34") (pin "1") (pinfunction "1A_1") (pintype "bidirectional"))
      (node (ref "JP2") (pin "6") (pinfunction "6_6") (pintype "passive"))
      (node (ref "JP3") (pin "6") (pinfunction "6_6") (pintype "passive"))
      (node (ref "R16") (pin "1") (pinfunction "1_1") (pintype "bidirectional"))
    )
    (net (code "114") (name "/D1_B18") (class "Default")
      (node (ref "IC2") (pin "4") (pinfunction "2A_4") (pintype "bidirectional"))
      (node (ref "IC34") (pin "4") (pinfunction "2A_4") (pintype "bidirectional"))
      (node (ref "JP2") (pin "8") (pinfunction "8_8") (pintype "passive"))
      (node (ref "JP3") (pin "8") (pinfunction "8_8") (pintype "passive"))
      (node (ref "R18") (pin "1") (pinfunction "1_1") (pintype "bidirectional"))
    )
    (net (code "115") (name "/D1_B19") (class "Default")
      (node (ref "IC2") (pin "12") (pinfunction "4A_12") (pintype "bidirectional"))
      (node (ref "IC34") (pin "13") (pinfunction "4B_13") (pintype "bidirectional"))
      (node (ref "JP2") (pin "10") (pinfunction "10_10") (pintype "passive"))
      (node (ref "JP3") (pin "10") (pinfunction "10_10") (pintype "passive"))
      (node (ref "R19") (pin "1") (pinfunction "1_1") (pintype "bidirectional"))
    )
    (net (code "116") (name "/D1_B20") (class "Default")
      (node (ref "IC2") (pin "9") (pinfunction "3A_9") (pintype "bidirectional"))
      (node (ref "IC34") (pin "10") (pinfunction "3B_10") (pintype "bidirectional"))
      (node (ref "JP2") (pin "12") (pinfunction "12_12") (pintype "passive"))
      (node (ref "JP3") (pin "12") (pinfunction "12_12") (pintype "passive"))
      (node (ref "R20") (pin "1") (pinfunction "1_1") (pintype "bidirectional"))
    )
    (net (code "117") (name "/D1_B21") (class "Default")
      (node (ref "IC36") (pin "1") (pinfunction "1A_1") (pintype "bidirectional"))
      (node (ref "IC4") (pin "1") (pinfunction "1A_1") (pintype "bidirectional"))
      (node (ref "JP2") (pin "14") (pinfunction "14_14") (pintype "passive"))
      (node (ref "JP3") (pin "14") (pinfunction "14_14") (pintype "passive"))
      (node (ref "R21") (pin "1") (pinfunction "1_1") (pintype "bidirectional"))
    )
    (net (code "118") (name "/D1_B22") (class "Default")
      (node (ref "IC36") (pin "4") (pinfunction "2A_4") (pintype "bidirectional"))
      (node (ref "IC4") (pin "4") (pinfunction "2A_4") (pintype "bidirectional"))
      (node (ref "JP2") (pin "16") (pinfunction "16_16") (pintype "passive"))
      (node (ref "JP3") (pin "16") (pinfunction "16_16") (pintype "passive"))
      (node (ref "R22") (pin "1") (pinfunction "1_1") (pintype "bidirectional"))
    )
    (net (code "119") (name "/D1_B23") (class "Default")
      (node (ref "IC36") (pin "13") (pinfunction "4B_13") (pintype "bidirectional"))
      (node (ref "IC4") (pin "12") (pinfunction "4A_12") (pintype "bidirectional"))
      (node (ref "JP2") (pin "18") (pinfunction "18_18") (pintype "passive"))
      (node (ref "JP3") (pin "18") (pinfunction "18_18") (pintype "passive"))
      (node (ref "R23") (pin "1") (pinfunction "1_1") (pintype "bidirectional"))
    )
    (net (code "120") (name "/D1_B24") (class "Default")
      (node (ref "IC36") (pin "10") (pinfunction "3B_10") (pintype "bidirectional"))
      (node (ref "IC4") (pin "9") (pinfunction "3A_9") (pintype "bidirectional"))
      (node (ref "JP2") (pin "20") (pinfunction "20_20") (pintype "passive"))
      (node (ref "JP3") (pin "20") (pinfunction "20_20") (pintype "passive"))
      (node (ref "R24") (pin "1") (pinfunction "1_1") (pintype "bidirectional"))
    )
    (net (code "121") (name "/D1_B25") (class "Default")
      (node (ref "IC38") (pin "1") (pinfunction "1A_1") (pintype "bidirectional"))
      (node (ref "IC6") (pin "1") (pinfunction "1A_1") (pintype "bidirectional"))
      (node (ref "JP2") (pin "22") (pinfunction "22_22") (pintype "passive"))
      (node (ref "JP3") (pin "22") (pinfunction "22_22") (pintype "passive"))
      (node (ref "R26") (pin "1") (pinfunction "1_1") (pintype "bidirectional"))
    )
    (net (code "122") (name "/D1_B26") (class "Default")
      (node (ref "IC38") (pin "4") (pinfunction "2A_4") (pintype "bidirectional"))
      (node (ref "IC6") (pin "4") (pinfunction "2A_4") (pintype "bidirectional"))
      (node (ref "JP2") (pin "24") (pinfunction "24_24") (pintype "passive"))
      (node (ref "JP3") (pin "24") (pinfunction "24_24") (pintype "passive"))
      (node (ref "R25") (pin "1") (pinfunction "1_1") (pintype "bidirectional"))
    )
    (net (code "123") (name "/D1_B27") (class "Default")
      (node (ref "IC38") (pin "13") (pinfunction "4B_13") (pintype "bidirectional"))
      (node (ref "IC6") (pin "12") (pinfunction "4A_12") (pintype "bidirectional"))
      (node (ref "JP2") (pin "26") (pinfunction "26_26") (pintype "passive"))
      (node (ref "JP3") (pin "26") (pinfunction "26_26") (pintype "passive"))
      (node (ref "R27") (pin "1") (pinfunction "1_1") (pintype "bidirectional"))
    )
    (net (code "124") (name "/D1_B28") (class "Default")
      (node (ref "IC38") (pin "10") (pinfunction "3B_10") (pintype "bidirectional"))
      (node (ref "IC6") (pin "9") (pinfunction "3A_9") (pintype "bidirectional"))
      (node (ref "JP2") (pin "28") (pinfunction "28_28") (pintype "passive"))
      (node (ref "JP3") (pin "28") (pinfunction "28_28") (pintype "passive"))
      (node (ref "R28") (pin "1") (pinfunction "1_1") (pintype "bidirectional"))
    )
    (net (code "125") (name "/D1_B29") (class "Default")
      (node (ref "IC40") (pin "1") (pinfunction "1A_1") (pintype "bidirectional"))
      (node (ref "IC8") (pin "1") (pinfunction "1A_1") (pintype "bidirectional"))
      (node (ref "JP2") (pin "30") (pinfunction "30_30") (pintype "passive"))
      (node (ref "JP3") (pin "30") (pinfunction "30_30") (pintype "passive"))
      (node (ref "R29") (pin "1") (pinfunction "1_1") (pintype "bidirectional"))
    )
    (net (code "126") (name "/D1_B30") (class "Default")
      (node (ref "IC40") (pin "4") (pinfunction "2A_4") (pintype "bidirectional"))
      (node (ref "IC8") (pin "4") (pinfunction "2A_4") (pintype "bidirectional"))
      (node (ref "JP2") (pin "32") (pinfunction "32_32") (pintype "passive"))
      (node (ref "JP3") (pin "32") (pinfunction "32_32") (pintype "passive"))
      (node (ref "R30") (pin "1") (pinfunction "1_1") (pintype "bidirectional"))
    )
    (net (code "127") (name "/D1_B31") (class "Default")
      (node (ref "IC40") (pin "13") (pinfunction "4B_13") (pintype "bidirectional"))
      (node (ref "IC8") (pin "12") (pinfunction "4A_12") (pintype "bidirectional"))
      (node (ref "JP2") (pin "34") (pinfunction "34_34") (pintype "passive"))
      (node (ref "JP3") (pin "34") (pinfunction "34_34") (pintype "passive"))
      (node (ref "R31") (pin "1") (pinfunction "1_1") (pintype "bidirectional"))
    )
    (net (code "128") (name "/D1_B32") (class "Default")
      (node (ref "IC40") (pin "10") (pinfunction "3B_10") (pintype "bidirectional"))
      (node (ref "IC8") (pin "9") (pinfunction "3A_9") (pintype "bidirectional"))
      (node (ref "JP2") (pin "36") (pinfunction "36_36") (pintype "passive"))
      (node (ref "JP3") (pin "36") (pinfunction "36_36") (pintype "passive"))
      (node (ref "R32") (pin "1") (pinfunction "1_1") (pintype "bidirectional"))
    )
    (net (code "129") (name "/D2_B1") (class "Default")
      (node (ref "IC17") (pin "1") (pinfunction "1A_1") (pintype "bidirectional"))
      (node (ref "IC33") (pin "2") (pinfunction "1B_2") (pintype "bidirectional"))
      (node (ref "JP1") (pin "5") (pinfunction "5_5") (pintype "passive"))
      (node (ref "JP4") (pin "5") (pinfunction "5_5") (pintype "passive"))
      (node (ref "R33") (pin "1") (pinfunction "1_1") (pintype "bidirectional"))
    )
    (net (code "130") (name "/D2_B2") (class "Default")
      (node (ref "IC17") (pin "4") (pinfunction "2A_4") (pintype "bidirectional"))
      (node (ref "IC33") (pin "5") (pinfunction "2B_5") (pintype "bidirectional"))
      (node (ref "JP1") (pin "7") (pinfunction "7_7") (pintype "passive"))
      (node (ref "JP4") (pin "7") (pinfunction "7_7") (pintype "passive"))
      (node (ref "R34") (pin "1") (pinfunction "1_1") (pintype "bidirectional"))
    )
    (net (code "131") (name "/D2_B3") (class "Default")
      (node (ref "IC17") (pin "12") (pinfunction "4A_12") (pintype "bidirectional"))
      (node (ref "IC33") (pin "12") (pinfunction "4A_12") (pintype "bidirectional"))
      (node (ref "JP1") (pin "9") (pinfunction "9_9") (pintype "passive"))
      (node (ref "JP4") (pin "9") (pinfunction "9_9") (pintype "passive"))
      (node (ref "R35") (pin "1") (pinfunction "1_1") (pintype "bidirectional"))
    )
    (net (code "132") (name "/D2_B4") (class "Default")
      (node (ref "IC17") (pin "9") (pinfunction "3A_9") (pintype "bidirectional"))
      (node (ref "IC33") (pin "9") (pinfunction "3A_9") (pintype "bidirectional"))
      (node (ref "JP1") (pin "11") (pinfunction "11_11") (pintype "passive"))
      (node (ref "JP4") (pin "11") (pinfunction "11_11") (pintype "passive"))
      (node (ref "R36") (pin "1") (pinfunction "1_1") (pintype "bidirectional"))
    )
    (net (code "133") (name "/D2_B5") (class "Default")
      (node (ref "IC19") (pin "1") (pinfunction "1A_1") (pintype "bidirectional"))
      (node (ref "IC35") (pin "2") (pinfunction "1B_2") (pintype "bidirectional"))
      (node (ref "JP1") (pin "13") (pinfunction "13_13") (pintype "passive"))
      (node (ref "JP4") (pin "13") (pinfunction "13_13") (pintype "passive"))
      (node (ref "R37") (pin "1") (pinfunction "1_1") (pintype "bidirectional"))
    )
    (net (code "134") (name "/D2_B6") (class "Default")
      (node (ref "IC19") (pin "4") (pinfunction "2A_4") (pintype "bidirectional"))
      (node (ref "IC35") (pin "5") (pinfunction "2B_5") (pintype "bidirectional"))
      (node (ref "JP1") (pin "15") (pinfunction "15_15") (pintype "passive"))
      (node (ref "JP4") (pin "15") (pinfunction "15_15") (pintype "passive"))
      (node (ref "R38") (pin "1") (pinfunction "1_1") (pintype "bidirectional"))
    )
    (net (code "135") (name "/D2_B7") (class "Default")
      (node (ref "IC19") (pin "12") (pinfunction "4A_12") (pintype "bidirectional"))
      (node (ref "IC35") (pin "12") (pinfunction "4A_12") (pintype "bidirectional"))
      (node (ref "JP1") (pin "17") (pinfunction "17_17") (pintype "passive"))
      (node (ref "JP4") (pin "17") (pinfunction "17_17") (pintype "passive"))
      (node (ref "R39") (pin "1") (pinfunction "1_1") (pintype "bidirectional"))
    )
    (net (code "136") (name "/D2_B8") (class "Default")
      (node (ref "IC19") (pin "9") (pinfunction "3A_9") (pintype "bidirectional"))
      (node (ref "IC35") (pin "9") (pinfunction "3A_9") (pintype "bidirectional"))
      (node (ref "JP1") (pin "19") (pinfunction "19_19") (pintype "passive"))
      (node (ref "JP4") (pin "19") (pinfunction "19_19") (pintype "passive"))
      (node (ref "R40") (pin "1") (pinfunction "1_1") (pintype "bidirectional"))
    )
    (net (code "137") (name "/D2_B9") (class "Default")
      (node (ref "IC21") (pin "1") (pinfunction "1A_1") (pintype "bidirectional"))
      (node (ref "IC37") (pin "2") (pinfunction "1B_2") (pintype "bidirectional"))
      (node (ref "JP1") (pin "21") (pinfunction "21_21") (pintype "passive"))
      (node (ref "JP4") (pin "21") (pinfunction "21_21") (pintype "passive"))
      (node (ref "R41") (pin "1") (pinfunction "1_1") (pintype "bidirectional"))
    )
    (net (code "138") (name "/D2_B10") (class "Default")
      (node (ref "IC21") (pin "4") (pinfunction "2A_4") (pintype "bidirectional"))
      (node (ref "IC37") (pin "5") (pinfunction "2B_5") (pintype "bidirectional"))
      (node (ref "JP1") (pin "23") (pinfunction "23_23") (pintype "passive"))
      (node (ref "JP4") (pin "23") (pinfunction "23_23") (pintype "passive"))
      (node (ref "R42") (pin "1") (pinfunction "1_1") (pintype "bidirectional"))
    )
    (net (code "139") (name "/D2_B11") (class "Default")
      (node (ref "IC21") (pin "12") (pinfunction "4A_12") (pintype "bidirectional"))
      (node (ref "IC37") (pin "12") (pinfunction "4A_12") (pintype "bidirectional"))
      (node (ref "JP1") (pin "25") (pinfunction "25_25") (pintype "passive"))
      (node (ref "JP4") (pin "25") (pinfunction "25_25") (pintype "passive"))
      (node (ref "R43") (pin "1") (pinfunction "1_1") (pintype "bidirectional"))
    )
    (net (code "140") (name "/D2_B12") (class "Default")
      (node (ref "IC21") (pin "9") (pinfunction "3A_9") (pintype "bidirectional"))
      (node (ref "IC37") (pin "9") (pinfunction "3A_9") (pintype "bidirectional"))
      (node (ref "JP1") (pin "27") (pinfunction "27_27") (pintype "passive"))
      (node (ref "JP4") (pin "27") (pinfunction "27_27") (pintype "passive"))
      (node (ref "R44") (pin "1") (pinfunction "1_1") (pintype "bidirectional"))
    )
    (net (code "141") (name "/D2_B13") (class "Default")
      (node (ref "IC23") (pin "1") (pinfunction "1A_1") (pintype "bidirectional"))
      (node (ref "IC39") (pin "2") (pinfunction "1B_2") (pintype "bidirectional"))
      (node (ref "JP1") (pin "29") (pinfunction "29_29") (pintype "passive"))
      (node (ref "JP4") (pin "29") (pinfunction "29_29") (pintype "passive"))
      (node (ref "R45") (pin "1") (pinfunction "1_1") (pintype "bidirectional"))
    )
    (net (code "142") (name "/D2_B14") (class "Default")
      (node (ref "IC23") (pin "4") (pinfunction "2A_4") (pintype "bidirectional"))
      (node (ref "IC39") (pin "5") (pinfunction "2B_5") (pintype "bidirectional"))
      (node (ref "JP1") (pin "31") (pinfunction "31_31") (pintype "passive"))
      (node (ref "JP4") (pin "31") (pinfunction "31_31") (pintype "passive"))
      (node (ref "R46") (pin "1") (pinfunction "1_1") (pintype "bidirectional"))
    )
    (net (code "143") (name "/D2_B15") (class "Default")
      (node (ref "IC23") (pin "12") (pinfunction "4A_12") (pintype "bidirectional"))
      (node (ref "IC39") (pin "12") (pinfunction "4A_12") (pintype "bidirectional"))
      (node (ref "JP1") (pin "33") (pinfunction "33_33") (pintype "passive"))
      (node (ref "JP4") (pin "33") (pinfunction "33_33") (pintype "passive"))
      (node (ref "R47") (pin "1") (pinfunction "1_1") (pintype "bidirectional"))
    )
    (net (code "144") (name "/D2_B16") (class "Default")
      (node (ref "IC23") (pin "9") (pinfunction "3A_9") (pintype "bidirectional"))
      (node (ref "IC39") (pin "9") (pinfunction "3A_9") (pintype "bidirectional"))
      (node (ref "JP1") (pin "35") (pinfunction "35_35") (pintype "passive"))
      (node (ref "JP4") (pin "35") (pinfunction "35_35") (pintype "passive"))
      (node (ref "R49") (pin "1") (pinfunction "1_1") (pintype "bidirectional"))
    )
    (net (code "145") (name "/D2_B17") (class "Default")
      (node (ref "IC18") (pin "1") (pinfunction "1A_1") (pintype "bidirectional"))
      (node (ref "IC34") (pin "2") (pinfunction "1B_2") (pintype "bidirectional"))
      (node (ref "JP1") (pin "6") (pinfunction "6_6") (pintype "passive"))
      (node (ref "JP4") (pin "6") (pinfunction "6_6") (pintype "passive"))
      (node (ref "R48") (pin "1") (pinfunction "1_1") (pintype "bidirectional"))
    )
    (net (code "146") (name "/D2_B18") (class "Default")
      (node (ref "IC18") (pin "4") (pinfunction "2A_4") (pintype "bidirectional"))
      (node (ref "IC34") (pin "5") (pinfunction "2B_5") (pintype "bidirectional"))
      (node (ref "JP1") (pin "8") (pinfunction "8_8") (pintype "passive"))
      (node (ref "JP4") (pin "8") (pinfunction "8_8") (pintype "passive"))
      (node (ref "R50") (pin "1") (pinfunction "1_1") (pintype "bidirectional"))
    )
    (net (code "147") (name "/D2_B19") (class "Default")
      (node (ref "IC18") (pin "12") (pinfunction "4A_12") (pintype "bidirectional"))
      (node (ref "IC34") (pin "12") (pinfunction "4A_12") (pintype "bidirectional"))
      (node (ref "JP1") (pin "10") (pinfunction "10_10") (pintype "passive"))
      (node (ref "JP4") (pin "10") (pinfunction "10_10") (pintype "passive"))
      (node (ref "R51") (pin "1") (pinfunction "1_1") (pintype "bidirectional"))
    )
    (net (code "148") (name "/D2_B20") (class "Default")
      (node (ref "IC18") (pin "9") (pinfunction "3A_9") (pintype "bidirectional"))
      (node (ref "IC34") (pin "9") (pinfunction "3A_9") (pintype "bidirectional"))
      (node (ref "JP1") (pin "12") (pinfunction "12_12") (pintype "passive"))
      (node (ref "JP4") (pin "12") (pinfunction "12_12") (pintype "passive"))
      (node (ref "R52") (pin "1") (pinfunction "1_1") (pintype "bidirectional"))
    )
    (net (code "149") (name "/D2_B21") (class "Default")
      (node (ref "IC20") (pin "1") (pinfunction "1A_1") (pintype "bidirectional"))
      (node (ref "IC36") (pin "2") (pinfunction "1B_2") (pintype "bidirectional"))
      (node (ref "JP1") (pin "14") (pinfunction "14_14") (pintype "passive"))
      (node (ref "JP4") (pin "14") (pinfunction "14_14") (pintype "passive"))
      (node (ref "R53") (pin "1") (pinfunction "1_1") (pintype "bidirectional"))
    )
    (net (code "150") (name "/D2_B22") (class "Default")
      (node (ref "IC20") (pin "4") (pinfunction "2A_4") (pintype "bidirectional"))
      (node (ref "IC36") (pin "5") (pinfunction "2B_5") (pintype "bidirectional"))
      (node (ref "JP1") (pin "16") (pinfunction "16_16") (pintype "passive"))
      (node (ref "JP4") (pin "16") (pinfunction "16_16") (pintype "passive"))
      (node (ref "R54") (pin "1") (pinfunction "1_1") (pintype "bidirectional"))
    )
    (net (code "151") (name "/D2_B23") (class "Default")
      (node (ref "IC20") (pin "12") (pinfunction "4A_12") (pintype "bidirectional"))
      (node (ref "IC36") (pin "12") (pinfunction "4A_12") (pintype "bidirectional"))
      (node (ref "JP1") (pin "18") (pinfunction "18_18") (pintype "passive"))
      (node (ref "JP4") (pin "18") (pinfunction "18_18") (pintype "passive"))
      (node (ref "R55") (pin "1") (pinfunction "1_1") (pintype "bidirectional"))
    )
    (net (code "152") (name "/D2_B24") (class "Default")
      (node (ref "IC20") (pin "9") (pinfunction "3A_9") (pintype "bidirectional"))
      (node (ref "IC36") (pin "9") (pinfunction "3A_9") (pintype "bidirectional"))
      (node (ref "JP1") (pin "20") (pinfunction "20_20") (pintype "passive"))
      (node (ref "JP4") (pin "20") (pinfunction "20_20") (pintype "passive"))
      (node (ref "R56") (pin "1") (pinfunction "1_1") (pintype "bidirectional"))
    )
    (net (code "153") (name "/D2_B25") (class "Default")
      (node (ref "IC22") (pin "1") (pinfunction "1A_1") (pintype "bidirectional"))
      (node (ref "IC38") (pin "2") (pinfunction "1B_2") (pintype "bidirectional"))
      (node (ref "JP1") (pin "22") (pinfunction "22_22") (pintype "passive"))
      (node (ref "JP4") (pin "22") (pinfunction "22_22") (pintype "passive"))
      (node (ref "R58") (pin "1") (pinfunction "1_1") (pintype "bidirectional"))
    )
    (net (code "154") (name "/D2_B26") (class "Default")
      (node (ref "IC22") (pin "4") (pinfunction "2A_4") (pintype "bidirectional"))
      (node (ref "IC38") (pin "5") (pinfunction "2B_5") (pintype "bidirectional"))
      (node (ref "JP1") (pin "24") (pinfunction "24_24") (pintype "passive"))
      (node (ref "JP4") (pin "24") (pinfunction "24_24") (pintype "passive"))
      (node (ref "R57") (pin "1") (pinfunction "1_1") (pintype "bidirectional"))
    )
    (net (code "155") (name "/D2_B27") (class "Default")
      (node (ref "IC22") (pin "12") (pinfunction "4A_12") (pintype "bidirectional"))
      (node (ref "IC38") (pin "12") (pinfunction "4A_12") (pintype "bidirectional"))
      (node (ref "JP1") (pin "26") (pinfunction "26_26") (pintype "passive"))
      (node (ref "JP4") (pin "26") (pinfunction "26_26") (pintype "passive"))
      (node (ref "R59") (pin "1") (pinfunction "1_1") (pintype "bidirectional"))
    )
    (net (code "156") (name "/D2_B28") (class "Default")
      (node (ref "IC22") (pin "9") (pinfunction "3A_9") (pintype "bidirectional"))
      (node (ref "IC38") (pin "9") (pinfunction "3A_9") (pintype "bidirectional"))
      (node (ref "JP1") (pin "28") (pinfunction "28_28") (pintype "passive"))
      (node (ref "JP4") (pin "28") (pinfunction "28_28") (pintype "passive"))
      (node (ref "R60") (pin "1") (pinfunction "1_1") (pintype "bidirectional"))
    )
    (net (code "157") (name "/D2_B29") (class "Default")
      (node (ref "IC24") (pin "1") (pinfunction "1A_1") (pintype "bidirectional"))
      (node (ref "IC40") (pin "2") (pinfunction "1B_2") (pintype "bidirectional"))
      (node (ref "JP1") (pin "30") (pinfunction "30_30") (pintype "passive"))
      (node (ref "JP4") (pin "30") (pinfunction "30_30") (pintype "passive"))
      (node (ref "R61") (pin "1") (pinfunction "1_1") (pintype "bidirectional"))
    )
    (net (code "158") (name "/D2_B30") (class "Default")
      (node (ref "IC24") (pin "4") (pinfunction "2A_4") (pintype "bidirectional"))
      (node (ref "IC40") (pin "5") (pinfunction "2B_5") (pintype "bidirectional"))
      (node (ref "JP1") (pin "32") (pinfunction "32_32") (pintype "passive"))
      (node (ref "JP4") (pin "32") (pinfunction "32_32") (pintype "passive"))
      (node (ref "R62") (pin "1") (pinfunction "1_1") (pintype "bidirectional"))
    )
    (net (code "159") (name "/D2_B31") (class "Default")
      (node (ref "IC24") (pin "12") (pinfunction "4A_12") (pintype "bidirectional"))
      (node (ref "IC40") (pin "12") (pinfunction "4A_12") (pintype "bidirectional"))
      (node (ref "JP1") (pin "34") (pinfunction "34_34") (pintype "passive"))
      (node (ref "JP4") (pin "34") (pinfunction "34_34") (pintype "passive"))
      (node (ref "R63") (pin "1") (pinfunction "1_1") (pintype "bidirectional"))
    )
    (net (code "160") (name "/D2_B32") (class "Default")
      (node (ref "IC24") (pin "9") (pinfunction "3A_9") (pintype "bidirectional"))
      (node (ref "IC40") (pin "9") (pinfunction "3A_9") (pintype "bidirectional"))
      (node (ref "JP1") (pin "36") (pinfunction "36_36") (pintype "passive"))
      (node (ref "JP4") (pin "36") (pinfunction "36_36") (pintype "passive"))
      (node (ref "R64") (pin "1") (pinfunction "1_1") (pintype "bidirectional"))
    )
    (net (code "161") (name "/INV_B1") (class "Default")
      (node (ref "IC1") (pin "2") (pinfunction "1B_2") (pintype "bidirectional"))
      (node (ref "IC17") (pin "3") (pinfunction "1Y_3") (pintype "bidirectional"))
    )
    (net (code "162") (name "/INV_B2") (class "Default")
      (node (ref "IC1") (pin "5") (pinfunction "2B_5") (pintype "bidirectional"))
      (node (ref "IC17") (pin "6") (pinfunction "2Y_6") (pintype "bidirectional"))
    )
    (net (code "163") (name "/INV_B3") (class "Default")
      (node (ref "IC1") (pin "13") (pinfunction "4B_13") (pintype "bidirectional"))
      (node (ref "IC17") (pin "11") (pinfunction "4Y_11") (pintype "bidirectional"))
    )
    (net (code "164") (name "/INV_B4") (class "Default")
      (node (ref "IC1") (pin "10") (pinfunction "3B_10") (pintype "bidirectional"))
      (node (ref "IC17") (pin "8") (pinfunction "3Y_8") (pintype "bidirectional"))
    )
    (net (code "165") (name "/INV_B5") (class "Default")
      (node (ref "IC19") (pin "3") (pinfunction "1Y_3") (pintype "bidirectional"))
      (node (ref "IC3") (pin "2") (pinfunction "1B_2") (pintype "bidirectional"))
    )
    (net (code "166") (name "/INV_B6") (class "Default")
      (node (ref "IC19") (pin "6") (pinfunction "2Y_6") (pintype "bidirectional"))
      (node (ref "IC3") (pin "5") (pinfunction "2B_5") (pintype "bidirectional"))
    )
    (net (code "167") (name "/INV_B7") (class "Default")
      (node (ref "IC19") (pin "11") (pinfunction "4Y_11") (pintype "bidirectional"))
      (node (ref "IC3") (pin "13") (pinfunction "4B_13") (pintype "bidirectional"))
    )
    (net (code "168") (name "/INV_B8") (class "Default")
      (node (ref "IC19") (pin "8") (pinfunction "3Y_8") (pintype "bidirectional"))
      (node (ref "IC3") (pin "10") (pinfunction "3B_10") (pintype "bidirectional"))
    )
    (net (code "169") (name "/INV_B9") (class "Default")
      (node (ref "IC21") (pin "3") (pinfunction "1Y_3") (pintype "bidirectional"))
      (node (ref "IC5") (pin "2") (pinfunction "1B_2") (pintype "bidirectional"))
    )
    (net (code "170") (name "/INV_B10") (class "Default")
      (node (ref "IC21") (pin "6") (pinfunction "2Y_6") (pintype "bidirectional"))
      (node (ref "IC5") (pin "5") (pinfunction "2B_5") (pintype "bidirectional"))
    )
    (net (code "171") (name "/INV_B11") (class "Default")
      (node (ref "IC21") (pin "11") (pinfunction "4Y_11") (pintype "bidirectional"))
      (node (ref "IC5") (pin "13") (pinfunction "4B_13") (pintype "bidirectional"))
    )
    (net (code "172") (name "/INV_B12") (class "Default")
      (node (ref "IC21") (pin "8") (pinfunction "3Y_8") (pintype "bidirectional"))
      (node (ref "IC5") (pin "10") (pinfunction "3B_10") (pintype "bidirectional"))
    )
    (net (code "173") (name "/INV_B13") (class "Default")
      (node (ref "IC23") (pin "3") (pinfunction "1Y_3") (pintype "bidirectional"))
      (node (ref "IC7") (pin "2") (pinfunction "1B_2") (pintype "bidirectional"))
    )
    (net (code "174") (name "/INV_B14") (class "Default")
      (node (ref "IC23") (pin "6") (pinfunction "2Y_6") (pintype "bidirectional"))
      (node (ref "IC7") (pin "5") (pinfunction "2B_5") (pintype "bidirectional"))
    )
    (net (code "175") (name "/INV_B15") (class "Default")
      (node (ref "IC23") (pin "11") (pinfunction "4Y_11") (pintype "bidirectional"))
      (node (ref "IC7") (pin "13") (pinfunction "4B_13") (pintype "bidirectional"))
    )
    (net (code "176") (name "/INV_B16") (class "Default")
      (node (ref "IC23") (pin "8") (pinfunction "3Y_8") (pintype "bidirectional"))
      (node (ref "IC7") (pin "10") (pinfunction "3B_10") (pintype "bidirectional"))
    )
    (net (code "177") (name "/INV_B17") (class "Default")
      (node (ref "IC18") (pin "3") (pinfunction "1Y_3") (pintype "bidirectional"))
      (node (ref "IC2") (pin "2") (pinfunction "1B_2") (pintype "bidirectional"))
    )
    (net (code "178") (name "/INV_B18") (class "Default")
      (node (ref "IC18") (pin "6") (pinfunction "2Y_6") (pintype "bidirectional"))
      (node (ref "IC2") (pin "5") (pinfunction "2B_5") (pintype "bidirectional"))
    )
    (net (code "179") (name "/INV_B19") (class "Default")
      (node (ref "IC18") (pin "11") (pinfunction "4Y_11") (pintype "bidirectional"))
      (node (ref "IC2") (pin "13") (pinfunction "4B_13") (pintype "bidirectional"))
    )
    (net (code "180") (name "/INV_B20") (class "Default")
      (node (ref "IC18") (pin "8") (pinfunction "3Y_8") (pintype "bidirectional"))
      (node (ref "IC2") (pin "10") (pinfunction "3B_10") (pintype "bidirectional"))
    )
    (net (code "181") (name "/INV_B21") (class "Default")
      (node (ref "IC20") (pin "3") (pinfunction "1Y_3") (pintype "bidirectional"))
      (node (ref "IC4") (pin "2") (pinfunction "1B_2") (pintype "bidirectional"))
    )
    (net (code "182") (name "/INV_B22") (class "Default")
      (node (ref "IC20") (pin "6") (pinfunction "2Y_6") (pintype "bidirectional"))
      (node (ref "IC4") (pin "5") (pinfunction "2B_5") (pintype "bidirectional"))
    )
    (net (code "183") (name "/INV_B23") (class "Default")
      (node (ref "IC20") (pin "11") (pinfunction "4Y_11") (pintype "bidirectional"))
      (node (ref "IC4") (pin "13") (pinfunction "4B_13") (pintype "bidirectional"))
    )
    (net (code "184") (name "/INV_B24") (class "Default")
      (node (ref "IC20") (pin "8") (pinfunction "3Y_8") (pintype "bidirectional"))
      (node (ref "IC4") (pin "10") (pinfunction "3B_10") (pintype "bidirectional"))
    )
    (net (code "185") (name "/INV_B25") (class "Default")
      (node (ref "IC22") (pin "3") (pinfunction "1Y_3") (pintype "bidirectional"))
      (node (ref "IC6") (pin "2") (pinfunction "1B_2") (pintype "bidirectional"))
    )
    (net (code "186") (name "/INV_B26") (class "Default")
      (node (ref "IC22") (pin "6") (pinfunction "2Y_6") (pintype "bidirectional"))
      (node (ref "IC6") (pin "5") (pinfunction "2B_5") (pintype "bidirectional"))
    )
    (net (code "187") (name "/INV_B27") (class "Default")
      (node (ref "IC22") (pin "11") (pinfunction "4Y_11") (pintype "bidirectional"))
      (node (ref "IC6") (pin "13") (pinfunction "4B_13") (pintype "bidirectional"))
    )
    (net (code "188") (name "/INV_B28") (class "Default")
      (node (ref "IC22") (pin "8") (pinfunction "3Y_8") (pintype "bidirectional"))
      (node (ref "IC6") (pin "10") (pinfunction "3B_10") (pintype "bidirectional"))
    )
    (net (code "189") (name "/INV_B29") (class "Default")
      (node (ref "IC24") (pin "3") (pinfunction "1Y_3") (pintype "bidirectional"))
      (node (ref "IC8") (pin "2") (pinfunction "1B_2") (pintype "bidirectional"))
    )
    (net (code "190") (name "/INV_B30") (class "Default")
      (node (ref "IC24") (pin "6") (pinfunction "2Y_6") (pintype "bidirectional"))
      (node (ref "IC8") (pin "5") (pinfunction "2B_5") (pintype "bidirectional"))
    )
    (net (code "191") (name "/INV_B31") (class "Default")
      (node (ref "IC24") (pin "11") (pinfunction "4Y_11") (pintype "bidirectional"))
      (node (ref "IC8") (pin "13") (pinfunction "4B_13") (pintype "bidirectional"))
    )
    (net (code "192") (name "/INV_B32") (class "Default")
      (node (ref "IC24") (pin "8") (pinfunction "3Y_8") (pintype "bidirectional"))
      (node (ref "IC8") (pin "10") (pinfunction "3B_10") (pintype "bidirectional"))
    )
    (net (code "193") (name "/SUB") (class "Default")
      (node (ref "IC17") (pin "10") (pinfunction "3B_10") (pintype "bidirectional"))
      (node (ref "IC17") (pin "13") (pinfunction "4B_13") (pintype "bidirectional"))
      (node (ref "IC17") (pin "2") (pinfunction "1B_2") (pintype "bidirectional"))
      (node (ref "IC17") (pin "5") (pinfunction "2B_5") (pintype "bidirectional"))
      (node (ref "IC18") (pin "10") (pinfunction "3B_10") (pintype "bidirectional"))
      (node (ref "IC18") (pin "13") (pinfunction "4B_13") (pintype "bidirectional"))
      (node (ref "IC18") (pin "2") (pinfunction "1B_2") (pintype "bidirectional"))
      (node (ref "IC18") (pin "5") (pinfunction "2B_5") (pintype "bidirectional"))
      (node (ref "IC19") (pin "10") (pinfunction "3B_10") (pintype "bidirectional"))
      (node (ref "IC19") (pin "13") (pinfunction "4B_13") (pintype "bidirectional"))
      (node (ref "IC19") (pin "2") (pinfunction "1B_2") (pintype "bidirectional"))
      (node (ref "IC19") (pin "5") (pinfunction "2B_5") (pintype "bidirectional"))
      (node (ref "IC20") (pin "10") (pinfunction "3B_10") (pintype "bidirectional"))
      (node (ref "IC20") (pin "13") (pinfunction "4B_13") (pintype "bidirectional"))
      (node (ref "IC20") (pin "2") (pinfunction "1B_2") (pintype "bidirectional"))
      (node (ref "IC20") (pin "5") (pinfunction "2B_5") (pintype "bidirectional"))
      (node (ref "IC21") (pin "10") (pinfunction "3B_10") (pintype "bidirectional"))
      (node (ref "IC21") (pin "13") (pinfunction "4B_13") (pintype "bidirectional"))
      (node (ref "IC21") (pin "2") (pinfunction "1B_2") (pintype "bidirectional"))
      (node (ref "IC21") (pin "5") (pinfunction "2B_5") (pintype "bidirectional"))
      (node (ref "IC22") (pin "10") (pinfunction "3B_10") (pintype "bidirectional"))
      (node (ref "IC22") (pin "13") (pinfunction "4B_13") (pintype "bidirectional"))
      (node (ref "IC22") (pin "2") (pinfunction "1B_2") (pintype "bidirectional"))
      (node (ref "IC22") (pin "5") (pinfunction "2B_5") (pintype "bidirectional"))
      (node (ref "IC23") (pin "10") (pinfunction "3B_10") (pintype "bidirectional"))
      (node (ref "IC23") (pin "13") (pinfunction "4B_13") (pintype "bidirectional"))
      (node (ref "IC23") (pin "2") (pinfunction "1B_2") (pintype "bidirectional"))
      (node (ref "IC23") (pin "5") (pinfunction "2B_5") (pintype "bidirectional"))
      (node (ref "IC24") (pin "10") (pinfunction "3B_10") (pintype "bidirectional"))
      (node (ref "IC24") (pin "13") (pinfunction "4B_13") (pintype "bidirectional"))
      (node (ref "IC24") (pin "2") (pinfunction "1B_2") (pintype "bidirectional"))
      (node (ref "IC24") (pin "5") (pinfunction "2B_5") (pintype "bidirectional"))
      (node (ref "IC25") (pin "2") (pinfunction "1B_2") (pintype "bidirectional"))
      (node (ref "IC9") (pin "2") (pinfunction "1B_2") (pintype "bidirectional"))
    )
    (net (code "194") (name "/SUM_B1") (class "Default")
      (node (ref "IC9") (pin "3") (pinfunction "1Y_3") (pintype "bidirectional"))
      (node (ref "JP5") (pin "5") (pinfunction "5_5") (pintype "passive"))
      (node (ref "JP6") (pin "5") (pinfunction "5_5") (pintype "passive"))
    )
    (net (code "195") (name "/SUM_B2") (class "Default")
      (node (ref "IC9") (pin "6") (pinfunction "2Y_6") (pintype "bidirectional"))
      (node (ref "JP5") (pin "7") (pinfunction "7_7") (pintype "passive"))
      (node (ref "JP6") (pin "7") (pinfunction "7_7") (pintype "passive"))
    )
    (net (code "196") (name "/SUM_B3") (class "Default")
      (node (ref "IC9") (pin "11") (pinfunction "4Y_11") (pintype "bidirectional"))
      (node (ref "JP5") (pin "9") (pinfunction "9_9") (pintype "passive"))
      (node (ref "JP6") (pin "9") (pinfunction "9_9") (pintype "passive"))
    )
    (net (code "197") (name "/SUM_B4") (class "Default")
      (node (ref "IC9") (pin "8") (pinfunction "3Y_8") (pintype "bidirectional"))
      (node (ref "JP5") (pin "11") (pinfunction "11_11") (pintype "passive"))
      (node (ref "JP6") (pin "11") (pinfunction "11_11") (pintype "passive"))
    )
    (net (code "198") (name "/SUM_B5") (class "Default")
      (node (ref "IC11") (pin "3") (pinfunction "1Y_3") (pintype "bidirectional"))
      (node (ref "JP5") (pin "13") (pinfunction "13_13") (pintype "passive"))
      (node (ref "JP6") (pin "13") (pinfunction "13_13") (pintype "passive"))
    )
    (net (code "199") (name "/SUM_B6") (class "Default")
      (node (ref "IC11") (pin "6") (pinfunction "2Y_6") (pintype "bidirectional"))
      (node (ref "JP5") (pin "15") (pinfunction "15_15") (pintype "passive"))
      (node (ref "JP6") (pin "15") (pinfunction "15_15") (pintype "passive"))
    )
    (net (code "200") (name "/SUM_B7") (class "Default")
      (node (ref "IC11") (pin "11") (pinfunction "4Y_11") (pintype "bidirectional"))
      (node (ref "JP5") (pin "17") (pinfunction "17_17") (pintype "passive"))
      (node (ref "JP6") (pin "17") (pinfunction "17_17") (pintype "passive"))
    )
    (net (code "201") (name "/SUM_B8") (class "Default")
      (node (ref "IC11") (pin "8") (pinfunction "3Y_8") (pintype "bidirectional"))
      (node (ref "JP5") (pin "19") (pinfunction "19_19") (pintype "passive"))
      (node (ref "JP6") (pin "19") (pinfunction "19_19") (pintype "passive"))
    )
    (net (code "202") (name "/SUM_B9") (class "Default")
      (node (ref "IC13") (pin "3") (pinfunction "1Y_3") (pintype "bidirectional"))
      (node (ref "JP5") (pin "21") (pinfunction "21_21") (pintype "passive"))
      (node (ref "JP6") (pin "21") (pinfunction "21_21") (pintype "passive"))
    )
    (net (code "203") (name "/SUM_B10") (class "Default")
      (node (ref "IC13") (pin "6") (pinfunction "2Y_6") (pintype "bidirectional"))
      (node (ref "JP5") (pin "23") (pinfunction "23_23") (pintype "passive"))
      (node (ref "JP6") (pin "23") (pinfunction "23_23") (pintype "passive"))
    )
    (net (code "204") (name "/SUM_B11") (class "Default")
      (node (ref "IC13") (pin "11") (pinfunction "4Y_11") (pintype "bidirectional"))
      (node (ref "JP5") (pin "25") (pinfunction "25_25") (pintype "passive"))
      (node (ref "JP6") (pin "25") (pinfunction "25_25") (pintype "passive"))
    )
    (net (code "205") (name "/SUM_B12") (class "Default")
      (node (ref "IC13") (pin "8") (pinfunction "3Y_8") (pintype "bidirectional"))
      (node (ref "JP5") (pin "27") (pinfunction "27_27") (pintype "passive"))
      (node (ref "JP6") (pin "27") (pinfunction "27_27") (pintype "passive"))
    )
    (net (code "206") (name "/SUM_B13") (class "Default")
      (node (ref "IC15") (pin "3") (pinfunction "1Y_3") (pintype "bidirectional"))
      (node (ref "JP5") (pin "29") (pinfunction "29_29") (pintype "passive"))
      (node (ref "JP6") (pin "29") (pinfunction "29_29") (pintype "passive"))
    )
    (net (code "207") (name "/SUM_B14") (class "Default")
      (node (ref "IC15") (pin "6") (pinfunction "2Y_6") (pintype "bidirectional"))
      (node (ref "JP5") (pin "31") (pinfunction "31_31") (pintype "passive"))
      (node (ref "JP6") (pin "31") (pinfunction "31_31") (pintype "passive"))
    )
    (net (code "208") (name "/SUM_B15") (class "Default")
      (node (ref "IC15") (pin "11") (pinfunction "4Y_11") (pintype "bidirectional"))
      (node (ref "JP5") (pin "33") (pinfunction "33_33") (pintype "passive"))
      (node (ref "JP6") (pin "33") (pinfunction "33_33") (pintype "passive"))
    )
    (net (code "209") (name "/SUM_B16") (class "Default")
      (node (ref "IC15") (pin "8") (pinfunction "3Y_8") (pintype "bidirectional"))
      (node (ref "JP5") (pin "35") (pinfunction "35_35") (pintype "passive"))
      (node (ref "JP6") (pin "35") (pinfunction "35_35") (pintype "passive"))
    )
    (net (code "210") (name "/SUM_B17") (class "Default")
      (node (ref "IC10") (pin "3") (pinfunction "1Y_3") (pintype "bidirectional"))
      (node (ref "JP5") (pin "6") (pinfunction "6_6") (pintype "passive"))
      (node (ref "JP6") (pin "6") (pinfunction "6_6") (pintype "passive"))
    )
    (net (code "211") (name "/SUM_B18") (class "Default")
      (node (ref "IC10") (pin "6") (pinfunction "2Y_6") (pintype "bidirectional"))
      (node (ref "JP5") (pin "8") (pinfunction "8_8") (pintype "passive"))
      (node (ref "JP6") (pin "8") (pinfunction "8_8") (pintype "passive"))
    )
    (net (code "212") (name "/SUM_B19") (class "Default")
      (node (ref "IC10") (pin "11") (pinfunction "4Y_11") (pintype "bidirectional"))
      (node (ref "JP5") (pin "10") (pinfunction "10_10") (pintype "passive"))
      (node (ref "JP6") (pin "10") (pinfunction "10_10") (pintype "passive"))
    )
    (net (code "213") (name "/SUM_B20") (class "Default")
      (node (ref "IC10") (pin "8") (pinfunction "3Y_8") (pintype "bidirectional"))
      (node (ref "JP5") (pin "12") (pinfunction "12_12") (pintype "passive"))
      (node (ref "JP6") (pin "12") (pinfunction "12_12") (pintype "passive"))
    )
    (net (code "214") (name "/SUM_B21") (class "Default")
      (node (ref "IC12") (pin "3") (pinfunction "1Y_3") (pintype "bidirectional"))
      (node (ref "JP5") (pin "14") (pinfunction "14_14") (pintype "passive"))
      (node (ref "JP6") (pin "14") (pinfunction "14_14") (pintype "passive"))
    )
    (net (code "215") (name "/SUM_B22") (class "Default")
      (node (ref "IC12") (pin "6") (pinfunction "2Y_6") (pintype "bidirectional"))
      (node (ref "JP5") (pin "16") (pinfunction "16_16") (pintype "passive"))
      (node (ref "JP6") (pin "16") (pinfunction "16_16") (pintype "passive"))
    )
    (net (code "216") (name "/SUM_B23") (class "Default")
      (node (ref "IC12") (pin "11") (pinfunction "4Y_11") (pintype "bidirectional"))
      (node (ref "JP5") (pin "18") (pinfunction "18_18") (pintype "passive"))
      (node (ref "JP6") (pin "18") (pinfunction "18_18") (pintype "passive"))
    )
    (net (code "217") (name "/SUM_B24") (class "Default")
      (node (ref "IC12") (pin "8") (pinfunction "3Y_8") (pintype "bidirectional"))
      (node (ref "JP5") (pin "20") (pinfunction "20_20") (pintype "passive"))
      (node (ref "JP6") (pin "20") (pinfunction "20_20") (pintype "passive"))
    )
    (net (code "218") (name "/SUM_B25") (class "Default")
      (node (ref "IC14") (pin "3") (pinfunction "1Y_3") (pintype "bidirectional"))
      (node (ref "JP5") (pin "22") (pinfunction "22_22") (pintype "passive"))
      (node (ref "JP6") (pin "22") (pinfunction "22_22") (pintype "passive"))
    )
    (net (code "219") (name "/SUM_B26") (class "Default")
      (node (ref "IC14") (pin "6") (pinfunction "2Y_6") (pintype "bidirectional"))
      (node (ref "JP5") (pin "24") (pinfunction "24_24") (pintype "passive"))
      (node (ref "JP6") (pin "24") (pinfunction "24_24") (pintype "passive"))
    )
    (net (code "220") (name "/SUM_B27") (class "Default")
      (node (ref "IC14") (pin "11") (pinfunction "4Y_11") (pintype "bidirectional"))
      (node (ref "JP5") (pin "26") (pinfunction "26_26") (pintype "passive"))
      (node (ref "JP6") (pin "26") (pinfunction "26_26") (pintype "passive"))
    )
    (net (code "221") (name "/SUM_B28") (class "Default")
      (node (ref "IC14") (pin "8") (pinfunction "3Y_8") (pintype "bidirectional"))
      (node (ref "JP5") (pin "28") (pinfunction "28_28") (pintype "passive"))
      (node (ref "JP6") (pin "28") (pinfunction "28_28") (pintype "passive"))
    )
    (net (code "222") (name "/SUM_B29") (class "Default")
      (node (ref "IC16") (pin "3") (pinfunction "1Y_3") (pintype "bidirectional"))
      (node (ref "JP5") (pin "30") (pinfunction "30_30") (pintype "passive"))
      (node (ref "JP6") (pin "30") (pinfunction "30_30") (pintype "passive"))
    )
    (net (code "223") (name "/SUM_B30") (class "Default")
      (node (ref "IC16") (pin "6") (pinfunction "2Y_6") (pintype "bidirectional"))
      (node (ref "JP5") (pin "32") (pinfunction "32_32") (pintype "passive"))
      (node (ref "JP6") (pin "32") (pinfunction "32_32") (pintype "passive"))
    )
    (net (code "224") (name "/SUM_B31") (class "Default")
      (node (ref "IC16") (pin "11") (pinfunction "4Y_11") (pintype "bidirectional"))
      (node (ref "JP5") (pin "34") (pinfunction "34_34") (pintype "passive"))
      (node (ref "JP6") (pin "34") (pinfunction "34_34") (pintype "passive"))
    )
    (net (code "225") (name "/SUM_B32") (class "Default")
      (node (ref "IC16") (pin "8") (pinfunction "3Y_8") (pintype "bidirectional"))
      (node (ref "JP5") (pin "36") (pinfunction "36_36") (pintype "passive"))
      (node (ref "JP6") (pin "36") (pinfunction "36_36") (pintype "passive"))
    )
    (net (code "226") (name "/XOR_B1") (class "Default")
      (node (ref "IC1") (pin "3") (pinfunction "1Y_3") (pintype "bidirectional"))
      (node (ref "IC25") (pin "1") (pinfunction "1A_1") (pintype "bidirectional"))
      (node (ref "IC9") (pin "1") (pinfunction "1A_1") (pintype "bidirectional"))
    )
    (net (code "227") (name "/XOR_B2") (class "Default")
      (node (ref "IC1") (pin "6") (pinfunction "2Y_6") (pintype "bidirectional"))
      (node (ref "IC25") (pin "4") (pinfunction "2A_4") (pintype "bidirectional"))
      (node (ref "IC9") (pin "4") (pinfunction "2A_4") (pintype "bidirectional"))
    )
    (net (code "228") (name "/XOR_B3") (class "Default")
      (node (ref "IC1") (pin "11") (pinfunction "4Y_11") (pintype "bidirectional"))
      (node (ref "IC25") (pin "13") (pinfunction "4B_13") (pintype "bidirectional"))
      (node (ref "IC9") (pin "12") (pinfunction "4A_12") (pintype "bidirectional"))
    )
    (net (code "229") (name "/XOR_B4") (class "Default")
      (node (ref "IC1") (pin "8") (pinfunction "3Y_8") (pintype "bidirectional"))
      (node (ref "IC25") (pin "10") (pinfunction "3B_10") (pintype "bidirectional"))
      (node (ref "IC9") (pin "9") (pinfunction "3A_9") (pintype "bidirectional"))
    )
    (net (code "230") (name "/XOR_B5") (class "Default")
      (node (ref "IC11") (pin "1") (pinfunction "1A_1") (pintype "bidirectional"))
      (node (ref "IC27") (pin "1") (pinfunction "1A_1") (pintype "bidirectional"))
      (node (ref "IC3") (pin "3") (pinfunction "1Y_3") (pintype "bidirectional"))
    )
    (net (code "231") (name "/XOR_B6") (class "Default")
      (node (ref "IC11") (pin "4") (pinfunction "2A_4") (pintype "bidirectional"))
      (node (ref "IC27") (pin "4") (pinfunction "2A_4") (pintype "bidirectional"))
      (node (ref "IC3") (pin "6") (pinfunction "2Y_6") (pintype "bidirectional"))
    )
    (net (code "232") (name "/XOR_B7") (class "Default")
      (node (ref "IC11") (pin "12") (pinfunction "4A_12") (pintype "bidirectional"))
      (node (ref "IC27") (pin "13") (pinfunction "4B_13") (pintype "bidirectional"))
      (node (ref "IC3") (pin "11") (pinfunction "4Y_11") (pintype "bidirectional"))
    )
    (net (code "233") (name "/XOR_B8") (class "Default")
      (node (ref "IC11") (pin "9") (pinfunction "3A_9") (pintype "bidirectional"))
      (node (ref "IC27") (pin "10") (pinfunction "3B_10") (pintype "bidirectional"))
      (node (ref "IC3") (pin "8") (pinfunction "3Y_8") (pintype "bidirectional"))
    )
    (net (code "234") (name "/XOR_B9") (class "Default")
      (node (ref "IC13") (pin "1") (pinfunction "1A_1") (pintype "bidirectional"))
      (node (ref "IC29") (pin "1") (pinfunction "1A_1") (pintype "bidirectional"))
      (node (ref "IC5") (pin "3") (pinfunction "1Y_3") (pintype "bidirectional"))
    )
    (net (code "235") (name "/XOR_B10") (class "Default")
      (node (ref "IC13") (pin "4") (pinfunction "2A_4") (pintype "bidirectional"))
      (node (ref "IC29") (pin "4") (pinfunction "2A_4") (pintype "bidirectional"))
      (node (ref "IC5") (pin "6") (pinfunction "2Y_6") (pintype "bidirectional"))
    )
    (net (code "236") (name "/XOR_B11") (class "Default")
      (node (ref "IC13") (pin "12") (pinfunction "4A_12") (pintype "bidirectional"))
      (node (ref "IC29") (pin "13") (pinfunction "4B_13") (pintype "bidirectional"))
      (node (ref "IC5") (pin "11") (pinfunction "4Y_11") (pintype "bidirectional"))
    )
    (net (code "237") (name "/XOR_B12") (class "Default")
      (node (ref "IC13") (pin "9") (pinfunction "3A_9") (pintype "bidirectional"))
      (node (ref "IC29") (pin "10") (pinfunction "3B_10") (pintype "bidirectional"))
      (node (ref "IC5") (pin "8") (pinfunction "3Y_8") (pintype "bidirectional"))
    )
    (net (code "238") (name "/XOR_B13") (class "Default")
      (node (ref "IC15") (pin "1") (pinfunction "1A_1") (pintype "bidirectional"))
      (node (ref "IC31") (pin "1") (pinfunction "1A_1") (pintype "bidirectional"))
      (node (ref "IC7") (pin "3") (pinfunction "1Y_3") (pintype "bidirectional"))
    )
    (net (code "239") (name "/XOR_B14") (class "Default")
      (node (ref "IC15") (pin "4") (pinfunction "2A_4") (pintype "bidirectional"))
      (node (ref "IC31") (pin "4") (pinfunction "2A_4") (pintype "bidirectional"))
      (node (ref "IC7") (pin "6") (pinfunction "2Y_6") (pintype "bidirectional"))
    )
    (net (code "240") (name "/XOR_B15") (class "Default")
      (node (ref "IC15") (pin "12") (pinfunction "4A_12") (pintype "bidirectional"))
      (node (ref "IC31") (pin "13") (pinfunction "4B_13") (pintype "bidirectional"))
      (node (ref "IC7") (pin "11") (pinfunction "4Y_11") (pintype "bidirectional"))
    )
    (net (code "241") (name "/XOR_B16") (class "Default")
      (node (ref "IC15") (pin "9") (pinfunction "3A_9") (pintype "bidirectional"))
      (node (ref "IC31") (pin "10") (pinfunction "3B_10") (pintype "bidirectional"))
      (node (ref "IC7") (pin "8") (pinfunction "3Y_8") (pintype "bidirectional"))
    )
    (net (code "242") (name "/XOR_B17") (class "Default")
      (node (ref "IC10") (pin "1") (pinfunction "1A_1") (pintype "bidirectional"))
      (node (ref "IC2") (pin "3") (pinfunction "1Y_3") (pintype "bidirectional"))
      (node (ref "IC26") (pin "1") (pinfunction "1A_1") (pintype "bidirectional"))
    )
    (net (code "243") (name "/XOR_B18") (class "Default")
      (node (ref "IC10") (pin "4") (pinfunction "2A_4") (pintype "bidirectional"))
      (node (ref "IC2") (pin "6") (pinfunction "2Y_6") (pintype "bidirectional"))
      (node (ref "IC26") (pin "4") (pinfunction "2A_4") (pintype "bidirectional"))
    )
    (net (code "244") (name "/XOR_B19") (class "Default")
      (node (ref "IC10") (pin "12") (pinfunction "4A_12") (pintype "bidirectional"))
      (node (ref "IC2") (pin "11") (pinfunction "4Y_11") (pintype "bidirectional"))
      (node (ref "IC26") (pin "13") (pinfunction "4B_13") (pintype "bidirectional"))
    )
    (net (code "245") (name "/XOR_B20") (class "Default")
      (node (ref "IC10") (pin "9") (pinfunction "3A_9") (pintype "bidirectional"))
      (node (ref "IC2") (pin "8") (pinfunction "3Y_8") (pintype "bidirectional"))
      (node (ref "IC26") (pin "10") (pinfunction "3B_10") (pintype "bidirectional"))
    )
    (net (code "246") (name "/XOR_B21") (class "Default")
      (node (ref "IC12") (pin "1") (pinfunction "1A_1") (pintype "bidirectional"))
      (node (ref "IC28") (pin "1") (pinfunction "1A_1") (pintype "bidirectional"))
      (node (ref "IC4") (pin "3") (pinfunction "1Y_3") (pintype "bidirectional"))
    )
    (net (code "247") (name "/XOR_B22") (class "Default")
      (node (ref "IC12") (pin "4") (pinfunction "2A_4") (pintype "bidirectional"))
      (node (ref "IC28") (pin "4") (pinfunction "2A_4") (pintype "bidirectional"))
      (node (ref "IC4") (pin "6") (pinfunction "2Y_6") (pintype "bidirectional"))
    )
    (net (code "248") (name "/XOR_B23") (class "Default")
      (node (ref "IC12") (pin "12") (pinfunction "4A_12") (pintype "bidirectional"))
      (node (ref "IC28") (pin "13") (pinfunction "4B_13") (pintype "bidirectional"))
      (node (ref "IC4") (pin "11") (pinfunction "4Y_11") (pintype "bidirectional"))
    )
    (net (code "249") (name "/XOR_B24") (class "Default")
      (node (ref "IC12") (pin "9") (pinfunction "3A_9") (pintype "bidirectional"))
      (node (ref "IC28") (pin "10") (pinfunction "3B_10") (pintype "bidirectional"))
      (node (ref "IC4") (pin "8") (pinfunction "3Y_8") (pintype "bidirectional"))
    )
    (net (code "250") (name "/XOR_B25") (class "Default")
      (node (ref "IC14") (pin "1") (pinfunction "1A_1") (pintype "bidirectional"))
      (node (ref "IC30") (pin "1") (pinfunction "1A_1") (pintype "bidirectional"))
      (node (ref "IC6") (pin "3") (pinfunction "1Y_3") (pintype "bidirectional"))
    )
    (net (code "251") (name "/XOR_B26") (class "Default")
      (node (ref "IC14") (pin "4") (pinfunction "2A_4") (pintype "bidirectional"))
      (node (ref "IC30") (pin "4") (pinfunction "2A_4") (pintype "bidirectional"))
      (node (ref "IC6") (pin "6") (pinfunction "2Y_6") (pintype "bidirectional"))
    )
    (net (code "252") (name "/XOR_B27") (class "Default")
      (node (ref "IC14") (pin "12") (pinfunction "4A_12") (pintype "bidirectional"))
      (node (ref "IC30") (pin "13") (pinfunction "4B_13") (pintype "bidirectional"))
      (node (ref "IC6") (pin "11") (pinfunction "4Y_11") (pintype "bidirectional"))
    )
    (net (code "253") (name "/XOR_B28") (class "Default")
      (node (ref "IC14") (pin "9") (pinfunction "3A_9") (pintype "bidirectional"))
      (node (ref "IC30") (pin "10") (pinfunction "3B_10") (pintype "bidirectional"))
      (node (ref "IC6") (pin "8") (pinfunction "3Y_8") (pintype "bidirectional"))
    )
    (net (code "254") (name "/XOR_B29") (class "Default")
      (node (ref "IC16") (pin "1") (pinfunction "1A_1") (pintype "bidirectional"))
      (node (ref "IC32") (pin "1") (pinfunction "1A_1") (pintype "bidirectional"))
      (node (ref "IC8") (pin "3") (pinfunction "1Y_3") (pintype "bidirectional"))
    )
    (net (code "255") (name "/XOR_B30") (class "Default")
      (node (ref "IC16") (pin "4") (pinfunction "2A_4") (pintype "bidirectional"))
      (node (ref "IC32") (pin "4") (pinfunction "2A_4") (pintype "bidirectional"))
      (node (ref "IC8") (pin "6") (pinfunction "2Y_6") (pintype "bidirectional"))
    )
    (net (code "256") (name "/XOR_B31") (class "Default")
      (node (ref "IC16") (pin "12") (pinfunction "4A_12") (pintype "bidirectional"))
      (node (ref "IC32") (pin "13") (pinfunction "4B_13") (pintype "bidirectional"))
      (node (ref "IC8") (pin "11") (pinfunction "4Y_11") (pintype "bidirectional"))
    )
    (net (code "257") (name "/XOR_B32") (class "Default")
      (node (ref "IC16") (pin "9") (pinfunction "3A_9") (pintype "bidirectional"))
      (node (ref "IC32") (pin "10") (pinfunction "3B_10") (pintype "bidirectional"))
      (node (ref "IC8") (pin "8") (pinfunction "3Y_8") (pintype "bidirectional"))
    )
    (net (code "258") (name "GND") (class "Default")
      (node (ref "C1") (pin "1") (pinfunction "1_1") (pintype "bidirectional"))
      (node (ref "C10") (pin "1") (pinfunction "1_1") (pintype "bidirectional"))
      (node (ref "C11") (pin "1") (pinfunction "1_1") (pintype "bidirectional"))
      (node (ref "C12") (pin "1") (pinfunction "1_1") (pintype "bidirectional"))
      (node (ref "C13") (pin "1") (pinfunction "1_1") (pintype "bidirectional"))
      (node (ref "C14") (pin "1") (pinfunction "1_1") (pintype "bidirectional"))
      (node (ref "C15") (pin "1") (pinfunction "1_1") (pintype "bidirectional"))
      (node (ref "C16") (pin "1") (pinfunction "1_1") (pintype "bidirectional"))
      (node (ref "C17") (pin "1") (pinfunction "1_1") (pintype "bidirectional"))
      (node (ref "C18") (pin "1") (pinfunction "1_1") (pintype "bidirectional"))
      (node (ref "C19") (pin "1") (pinfunction "1_1") (pintype "bidirectional"))
      (node (ref "C2") (pin "1") (pinfunction "1_1") (pintype "bidirectional"))
      (node (ref "C20") (pin "1") (pinfunction "1_1") (pintype "bidirectional"))
      (node (ref "C21") (pin "1") (pinfunction "1_1") (pintype "bidirectional"))
      (node (ref "C22") (pin "1") (pinfunction "1_1") (pintype "bidirectional"))
      (node (ref "C23") (pin "1") (pinfunction "1_1") (pintype "bidirectional"))
      (node (ref "C24") (pin "1") (pinfunction "1_1") (pintype "bidirectional"))
      (node (ref "C3") (pin "1") (pinfunction "1_1") (pintype "bidirectional"))
      (node (ref "C4") (pin "1") (pinfunction "1_1") (pintype "bidirectional"))
      (node (ref "C5") (pin "1") (pinfunction "1_1") (pintype "bidirectional"))
      (node (ref "C6") (pin "1") (pinfunction "1_1") (pintype "bidirectional"))
      (node (ref "C7") (pin "1") (pinfunction "1_1") (pintype "bidirectional"))
      (node (ref "C8") (pin "1") (pinfunction "1_1") (pintype "bidirectional"))
      (node (ref "C9") (pin "1") (pinfunction "1_1") (pintype "bidirectional"))
      (node (ref "IC1") (pin "7") (pinfunction "GND_7") (pintype "bidirectional"))
      (node (ref "IC10") (pin "7") (pinfunction "GND_7") (pintype "bidirectional"))
      (node (ref "IC11") (pin "7") (pinfunction "GND_7") (pintype "bidirectional"))
      (node (ref "IC12") (pin "7") (pinfunction "GND_7") (pintype "bidirectional"))
      (node (ref "IC13") (pin "7") (pinfunction "GND_7") (pintype "bidirectional"))
      (node (ref "IC14") (pin "7") (pinfunction "GND_7") (pintype "bidirectional"))
      (node (ref "IC15") (pin "7") (pinfunction "GND_7") (pintype "bidirectional"))
      (node (ref "IC16") (pin "7") (pinfunction "GND_7") (pintype "bidirectional"))
      (node (ref "IC17") (pin "7") (pinfunction "GND_7") (pintype "bidirectional"))
      (node (ref "IC18") (pin "7") (pinfunction "GND_7") (pintype "bidirectional"))
      (node (ref "IC19") (pin "7") (pinfunction "GND_7") (pintype "bidirectional"))
      (node (ref "IC2") (pin "7") (pinfunction "GND_7") (pintype "bidirectional"))
      (node (ref "IC20") (pin "7") (pinfunction "GND_7") (pintype "bidirectional"))
      (node (ref "IC21") (pin "7") (pinfunction "GND_7") (pintype "bidirectional"))
      (node (ref "IC22") (pin "7") (pinfunction "GND_7") (pintype "bidirectional"))
      (node (ref "IC23") (pin "7") (pinfunction "GND_7") (pintype "bidirectional"))
      (node (ref "IC24") (pin "7") (pinfunction "GND_7") (pintype "bidirectional"))
      (node (ref "IC25") (pin "7") (pinfunction "GND_7") (pintype "bidirectional"))
      (node (ref "IC26") (pin "7") (pinfunction "GND_7") (pintype "bidirectional"))
      (node (ref "IC27") (pin "7") (pinfunction "GND_7") (pintype "bidirectional"))
      (node (ref "IC28") (pin "7") (pinfunction "GND_7") (pintype "bidirectional"))
      (node (ref "IC29") (pin "7") (pinfunction "GND_7") (pintype "bidirectional"))
      (node (ref "IC3") (pin "7") (pinfunction "GND_7") (pintype "bidirectional"))
      (node (ref "IC30") (pin "7") (pinfunction "GND_7") (pintype "bidirectional"))
      (node (ref "IC31") (pin "7") (pinfunction "GND_7") (pintype "bidirectional"))
      (node (ref "IC32") (pin "7") (pinfunction "GND_7") (pintype "bidirectional"))
      (node (ref "IC33") (pin "7") (pinfunction "GND_7") (pintype "bidirectional"))
      (node (ref "IC34") (pin "7") (pinfunction "GND_7") (pintype "bidirectional"))
      (node (ref "IC35") (pin "7") (pinfunction "GND_7") (pintype "bidirectional"))
      (node (ref "IC36") (pin "7") (pinfunction "GND_7") (pintype "bidirectional"))
      (node (ref "IC37") (pin "7") (pinfunction "GND_7") (pintype "bidirectional"))
      (node (ref "IC38") (pin "7") (pinfunction "GND_7") (pintype "bidirectional"))
      (node (ref "IC39") (pin "7") (pinfunction "GND_7") (pintype "bidirectional"))
      (node (ref "IC4") (pin "7") (pinfunction "GND_7") (pintype "bidirectional"))
      (node (ref "IC40") (pin "7") (pinfunction "GND_7") (pintype "bidirectional"))
      (node (ref "IC41") (pin "7") (pinfunction "GND_7") (pintype "bidirectional"))
      (node (ref "IC42") (pin "7") (pinfunction "GND_7") (pintype "bidirectional"))
      (node (ref "IC43") (pin "7") (pinfunction "GND_7") (pintype "bidirectional"))
      (node (ref "IC44") (pin "7") (pinfunction "GND_7") (pintype "bidirectional"))
      (node (ref "IC45") (pin "7") (pinfunction "GND_7") (pintype "bidirectional"))
      (node (ref "IC46") (pin "7") (pinfunction "GND_7") (pintype "bidirectional"))
      (node (ref "IC47") (pin "7") (pinfunction "GND_7") (pintype "bidirectional"))
      (node (ref "IC48") (pin "7") (pinfunction "GND_7") (pintype "bidirectional"))
      (node (ref "IC5") (pin "7") (pinfunction "GND_7") (pintype "bidirectional"))
      (node (ref "IC6") (pin "7") (pinfunction "GND_7") (pintype "bidirectional"))
      (node (ref "IC7") (pin "7") (pinfunction "GND_7") (pintype "bidirectional"))
      (node (ref "IC8") (pin "7") (pinfunction "GND_7") (pintype "bidirectional"))
      (node (ref "IC9") (pin "7") (pinfunction "GND_7") (pintype "bidirectional"))
      (node (ref "JP1") (pin "3") (pinfunction "3_3") (pintype "passive"))
      (node (ref "JP1") (pin "37") (pinfunction "37_37") (pintype "passive"))
      (node (ref "JP1") (pin "38") (pinfunction "38_38") (pintype "passive"))
      (node (ref "JP1") (pin "4") (pinfunction "4_4") (pintype "passive"))
      (node (ref "JP2") (pin "3") (pinfunction "3_3") (pintype "passive"))
      (node (ref "JP2") (pin "37") (pinfunction "37_37") (pintype "passive"))
      (node (ref "JP2") (pin "38") (pinfunction "38_38") (pintype "passive"))
      (node (ref "JP2") (pin "4") (pinfunction "4_4") (pintype "passive"))
      (node (ref "JP3") (pin "3") (pinfunction "3_3") (pintype "passive"))
      (node (ref "JP3") (pin "37") (pinfunction "37_37") (pintype "passive"))
      (node (ref "JP3") (pin "38") (pinfunction "38_38") (pintype "passive"))
      (node (ref "JP3") (pin "4") (pinfunction "4_4") (pintype "passive"))
      (node (ref "JP4") (pin "3") (pinfunction "3_3") (pintype "passive"))
      (node (ref "JP4") (pin "37") (pinfunction "37_37") (pintype "passive"))
      (node (ref "JP4") (pin "38") (pinfunction "38_38") (pintype "passive"))
      (node (ref "JP4") (pin "4") (pinfunction "4_4") (pintype "passive"))
      (node (ref "JP5") (pin "3") (pinfunction "3_3") (pintype "passive"))
      (node (ref "JP5") (pin "37") (pinfunction "37_37") (pintype "passive"))
      (node (ref "JP5") (pin "38") (pinfunction "38_38") (pintype "passive"))
      (node (ref "JP5") (pin "4") (pinfunction "4_4") (pintype "passive"))
      (node (ref "JP6") (pin "3") (pinfunction "3_3") (pintype "passive"))
      (node (ref "JP6") (pin "37") (pinfunction "37_37") (pintype "passive"))
      (node (ref "JP6") (pin "38") (pinfunction "38_38") (pintype "passive"))
      (node (ref "JP6") (pin "4") (pinfunction "4_4") (pintype "passive"))
      (node (ref "R1") (pin "2") (pinfunction "2_2") (pintype "bidirectional"))
      (node (ref "R10") (pin "2") (pinfunction "2_2") (pintype "bidirectional"))
      (node (ref "R11") (pin "2") (pinfunction "2_2") (pintype "bidirectional"))
      (node (ref "R12") (pin "2") (pinfunction "2_2") (pintype "bidirectional"))
      (node (ref "R13") (pin "2") (pinfunction "2_2") (pintype "bidirectional"))
      (node (ref "R14") (pin "2") (pinfunction "2_2") (pintype "bidirectional"))
      (node (ref "R15") (pin "2") (pinfunction "2_2") (pintype "bidirectional"))
      (node (ref "R16") (pin "2") (pinfunction "2_2") (pintype "bidirectional"))
      (node (ref "R17") (pin "2") (pinfunction "2_2") (pintype "bidirectional"))
      (node (ref "R18") (pin "2") (pinfunction "2_2") (pintype "bidirectional"))
      (node (ref "R19") (pin "2") (pinfunction "2_2") (pintype "bidirectional"))
      (node (ref "R2") (pin "2") (pinfunction "2_2") (pintype "bidirectional"))
      (node (ref "R20") (pin "2") (pinfunction "2_2") (pintype "bidirectional"))
      (node (ref "R21") (pin "2") (pinfunction "2_2") (pintype "bidirectional"))
      (node (ref "R22") (pin "2") (pinfunction "2_2") (pintype "bidirectional"))
      (node (ref "R23") (pin "2") (pinfunction "2_2") (pintype "bidirectional"))
      (node (ref "R24") (pin "2") (pinfunction "2_2") (pintype "bidirectional"))
      (node (ref "R25") (pin "2") (pinfunction "2_2") (pintype "bidirectional"))
      (node (ref "R26") (pin "2") (pinfunction "2_2") (pintype "bidirectional"))
      (node (ref "R27") (pin "2") (pinfunction "2_2") (pintype "bidirectional"))
      (node (ref "R28") (pin "2") (pinfunction "2_2") (pintype "bidirectional"))
      (node (ref "R29") (pin "2") (pinfunction "2_2") (pintype "bidirectional"))
      (node (ref "R3") (pin "2") (pinfunction "2_2") (pintype "bidirectional"))
      (node (ref "R30") (pin "2") (pinfunction "2_2") (pintype "bidirectional"))
      (node (ref "R31") (pin "2") (pinfunction "2_2") (pintype "bidirectional"))
      (node (ref "R32") (pin "2") (pinfunction "2_2") (pintype "bidirectional"))
      (node (ref "R33") (pin "2") (pinfunction "2_2") (pintype "bidirectional"))
      (node (ref "R34") (pin "2") (pinfunction "2_2") (pintype "bidirectional"))
      (node (ref "R35") (pin "2") (pinfunction "2_2") (pintype "bidirectional"))
      (node (ref "R36") (pin "2") (pinfunction "2_2") (pintype "bidirectional"))
      (node (ref "R37") (pin "2") (pinfunction "2_2") (pintype "bidirectional"))
      (node (ref "R38") (pin "2") (pinfunction "2_2") (pintype "bidirectional"))
      (node (ref "R39") (pin "2") (pinfunction "2_2") (pintype "bidirectional"))
      (node (ref "R4") (pin "2") (pinfunction "2_2") (pintype "bidirectional"))
      (node (ref "R40") (pin "2") (pinfunction "2_2") (pintype "bidirectional"))
      (node (ref "R41") (pin "2") (pinfunction "2_2") (pintype "bidirectional"))
      (node (ref "R42") (pin "2") (pinfunction "2_2") (pintype "bidirectional"))
      (node (ref "R43") (pin "2") (pinfunction "2_2") (pintype "bidirectional"))
      (node (ref "R44") (pin "2") (pinfunction "2_2") (pintype "bidirectional"))
      (node (ref "R45") (pin "2") (pinfunction "2_2") (pintype "bidirectional"))
      (node (ref "R46") (pin "2") (pinfunction "2_2") (pintype "bidirectional"))
      (node (ref "R47") (pin "2") (pinfunction "2_2") (pintype "bidirectional"))
      (node (ref "R48") (pin "2") (pinfunction "2_2") (pintype "bidirectional"))
      (node (ref "R49") (pin "2") (pinfunction "2_2") (pintype "bidirectional"))
      (node (ref "R5") (pin "2") (pinfunction "2_2") (pintype "bidirectional"))
      (node (ref "R50") (pin "2") (pinfunction "2_2") (pintype "bidirectional"))
      (node (ref "R51") (pin "2") (pinfunction "2_2") (pintype "bidirectional"))
      (node (ref "R52") (pin "2") (pinfunction "2_2") (pintype "bidirectional"))
      (node (ref "R53") (pin "2") (pinfunction "2_2") (pintype "bidirectional"))
      (node (ref "R54") (pin "2") (pinfunction "2_2") (pintype "bidirectional"))
      (node (ref "R55") (pin "2") (pinfunction "2_2") (pintype "bidirectional"))
      (node (ref "R56") (pin "2") (pinfunction "2_2") (pintype "bidirectional"))
      (node (ref "R57") (pin "2") (pinfunction "2_2") (pintype "bidirectional"))
      (node (ref "R58") (pin "2") (pinfunction "2_2") (pintype "bidirectional"))
      (node (ref "R59") (pin "2") (pinfunction "2_2") (pintype "bidirectional"))
      (node (ref "R6") (pin "2") (pinfunction "2_2") (pintype "bidirectional"))
      (node (ref "R60") (pin "2") (pinfunction "2_2") (pintype "bidirectional"))
      (node (ref "R61") (pin "2") (pinfunction "2_2") (pintype "bidirectional"))
      (node (ref "R62") (pin "2") (pinfunction "2_2") (pintype "bidirectional"))
      (node (ref "R63") (pin "2") (pinfunction "2_2") (pintype "bidirectional"))
      (node (ref "R64") (pin "2") (pinfunction "2_2") (pintype "bidirectional"))
      (node (ref "R7") (pin "2") (pinfunction "2_2") (pintype "bidirectional"))
      (node (ref "R8") (pin "2") (pinfunction "2_2") (pintype "bidirectional"))
      (node (ref "R9") (pin "2") (pinfunction "2_2") (pintype "bidirectional"))
    )
    (net (code "259") (name "VCC") (class "Default")
      (node (ref "C1") (pin "2") (pinfunction "2_2") (pintype "bidirectional"))
      (node (ref "C10") (pin "2") (pinfunction "2_2") (pintype "bidirectional"))
      (node (ref "C11") (pin "2") (pinfunction "2_2") (pintype "bidirectional"))
      (node (ref "C12") (pin "2") (pinfunction "2_2") (pintype "bidirectional"))
      (node (ref "C13") (pin "2") (pinfunction "2_2") (pintype "bidirectional"))
      (node (ref "C14") (pin "2") (pinfunction "2_2") (pintype "bidirectional"))
      (node (ref "C15") (pin "2") (pinfunction "2_2") (pintype "bidirectional"))
      (node (ref "C16") (pin "2") (pinfunction "2_2") (pintype "bidirectional"))
      (node (ref "C17") (pin "2") (pinfunction "2_2") (pintype "bidirectional"))
      (node (ref "C18") (pin "2") (pinfunction "2_2") (pintype "bidirectional"))
      (node (ref "C19") (pin "2") (pinfunction "2_2") (pintype "bidirectional"))
      (node (ref "C2") (pin "2") (pinfunction "2_2") (pintype "bidirectional"))
      (node (ref "C20") (pin "2") (pinfunction "2_2") (pintype "bidirectional"))
      (node (ref "C21") (pin "2") (pinfunction "2_2") (pintype "bidirectional"))
      (node (ref "C22") (pin "2") (pinfunction "2_2") (pintype "bidirectional"))
      (node (ref "C23") (pin "2") (pinfunction "2_2") (pintype "bidirectional"))
      (node (ref "C24") (pin "2") (pinfunction "2_2") (pintype "bidirectional"))
      (node (ref "C3") (pin "2") (pinfunction "2_2") (pintype "bidirectional"))
      (node (ref "C4") (pin "2") (pinfunction "2_2") (pintype "bidirectional"))
      (node (ref "C5") (pin "2") (pinfunction "2_2") (pintype "bidirectional"))
      (node (ref "C6") (pin "2") (pinfunction "2_2") (pintype "bidirectional"))
      (node (ref "C7") (pin "2") (pinfunction "2_2") (pintype "bidirectional"))
      (node (ref "C8") (pin "2") (pinfunction "2_2") (pintype "bidirectional"))
      (node (ref "C9") (pin "2") (pinfunction "2_2") (pintype "bidirectional"))
      (node (ref "IC1") (pin "14") (pinfunction "VCC_14") (pintype "bidirectional"))
      (node (ref "IC10") (pin "14") (pinfunction "VCC_14") (pintype "bidirectional"))
      (node (ref "IC11") (pin "14") (pinfunction "VCC_14") (pintype "bidirectional"))
      (node (ref "IC12") (pin "14") (pinfunction "VCC_14") (pintype "bidirectional"))
      (node (ref "IC13") (pin "14") (pinfunction "VCC_14") (pintype "bidirectional"))
      (node (ref "IC14") (pin "14") (pinfunction "VCC_14") (pintype "bidirectional"))
      (node (ref "IC15") (pin "14") (pinfunction "VCC_14") (pintype "bidirectional"))
      (node (ref "IC16") (pin "14") (pinfunction "VCC_14") (pintype "bidirectional"))
      (node (ref "IC17") (pin "14") (pinfunction "VCC_14") (pintype "bidirectional"))
      (node (ref "IC18") (pin "14") (pinfunction "VCC_14") (pintype "bidirectional"))
      (node (ref "IC19") (pin "14") (pinfunction "VCC_14") (pintype "bidirectional"))
      (node (ref "IC2") (pin "14") (pinfunction "VCC_14") (pintype "bidirectional"))
      (node (ref "IC20") (pin "14") (pinfunction "VCC_14") (pintype "bidirectional"))
      (node (ref "IC21") (pin "14") (pinfunction "VCC_14") (pintype "bidirectional"))
      (node (ref "IC22") (pin "14") (pinfunction "VCC_14") (pintype "bidirectional"))
      (node (ref "IC23") (pin "14") (pinfunction "VCC_14") (pintype "bidirectional"))
      (node (ref "IC24") (pin "14") (pinfunction "VCC_14") (pintype "bidirectional"))
      (node (ref "IC25") (pin "14") (pinfunction "VCC_14") (pintype "bidirectional"))
      (node (ref "IC26") (pin "14") (pinfunction "VCC_14") (pintype "bidirectional"))
      (node (ref "IC27") (pin "14") (pinfunction "VCC_14") (pintype "bidirectional"))
      (node (ref "IC28") (pin "14") (pinfunction "VCC_14") (pintype "bidirectional"))
      (node (ref "IC29") (pin "14") (pinfunction "VCC_14") (pintype "bidirectional"))
      (node (ref "IC3") (pin "14") (pinfunction "VCC_14") (pintype "bidirectional"))
      (node (ref "IC30") (pin "14") (pinfunction "VCC_14") (pintype "bidirectional"))
      (node (ref "IC31") (pin "14") (pinfunction "VCC_14") (pintype "bidirectional"))
      (node (ref "IC32") (pin "14") (pinfunction "VCC_14") (pintype "bidirectional"))
      (node (ref "IC33") (pin "14") (pinfunction "VCC_14") (pintype "bidirectional"))
      (node (ref "IC34") (pin "14") (pinfunction "VCC_14") (pintype "bidirectional"))
      (node (ref "IC35") (pin "14") (pinfunction "VCC_14") (pintype "bidirectional"))
      (node (ref "IC36") (pin "14") (pinfunction "VCC_14") (pintype "bidirectional"))
      (node (ref "IC37") (pin "14") (pinfunction "VCC_14") (pintype "bidirectional"))
      (node (ref "IC38") (pin "14") (pinfunction "VCC_14") (pintype "bidirectional"))
      (node (ref "IC39") (pin "14") (pinfunction "VCC_14") (pintype "bidirectional"))
      (node (ref "IC4") (pin "14") (pinfunction "VCC_14") (pintype "bidirectional"))
      (node (ref "IC40") (pin "14") (pinfunction "VCC_14") (pintype "bidirectional"))
      (node (ref "IC41") (pin "14") (pinfunction "VCC_14") (pintype "bidirectional"))
      (node (ref "IC42") (pin "14") (pinfunction "VCC_14") (pintype "bidirectional"))
      (node (ref "IC43") (pin "14") (pinfunction "VCC_14") (pintype "bidirectional"))
      (node (ref "IC44") (pin "14") (pinfunction "VCC_14") (pintype "bidirectional"))
      (node (ref "IC45") (pin "14") (pinfunction "VCC_14") (pintype "bidirectional"))
      (node (ref "IC46") (pin "14") (pinfunction "VCC_14") (pintype "bidirectional"))
      (node (ref "IC47") (pin "14") (pinfunction "VCC_14") (pintype "bidirectional"))
      (node (ref "IC48") (pin "14") (pinfunction "VCC_14") (pintype "bidirectional"))
      (node (ref "IC5") (pin "14") (pinfunction "VCC_14") (pintype "bidirectional"))
      (node (ref "IC6") (pin "14") (pinfunction "VCC_14") (pintype "bidirectional"))
      (node (ref "IC7") (pin "14") (pinfunction "VCC_14") (pintype "bidirectional"))
      (node (ref "IC8") (pin "14") (pinfunction "VCC_14") (pintype "bidirectional"))
      (node (ref "IC9") (pin "14") (pinfunction "VCC_14") (pintype "bidirectional"))
      (node (ref "JP1") (pin "1") (pinfunction "1_1") (pintype "passive"))
      (node (ref "JP1") (pin "2") (pinfunction "2_2") (pintype "passive"))
      (node (ref "JP1") (pin "39") (pinfunction "39_39") (pintype "passive"))
      (node (ref "JP1") (pin "40") (pinfunction "40_40") (pintype "passive"))
      (node (ref "JP2") (pin "1") (pinfunction "1_1") (pintype "passive"))
      (node (ref "JP2") (pin "2") (pinfunction "2_2") (pintype "passive"))
      (node (ref "JP2") (pin "39") (pinfunction "39_39") (pintype "passive"))
      (node (ref "JP2") (pin "40") (pinfunction "40_40") (pintype "passive"))
      (node (ref "JP3") (pin "1") (pinfunction "1_1") (pintype "passive"))
      (node (ref "JP3") (pin "2") (pinfunction "2_2") (pintype "passive"))
      (node (ref "JP3") (pin "39") (pinfunction "39_39") (pintype "passive"))
      (node (ref "JP3") (pin "40") (pinfunction "40_40") (pintype "passive"))
      (node (ref "JP4") (pin "1") (pinfunction "1_1") (pintype "passive"))
      (node (ref "JP4") (pin "2") (pinfunction "2_2") (pintype "passive"))
      (node (ref "JP4") (pin "39") (pinfunction "39_39") (pintype "passive"))
      (node (ref "JP4") (pin "40") (pinfunction "40_40") (pintype "passive"))
      (node (ref "JP5") (pin "1") (pinfunction "1_1") (pintype "passive"))
      (node (ref "JP5") (pin "2") (pinfunction "2_2") (pintype "passive"))
      (node (ref "JP5") (pin "39") (pinfunction "39_39") (pintype "passive"))
      (node (ref "JP5") (pin "40") (pinfunction "40_40") (pintype "passive"))
      (node (ref "JP6") (pin "1") (pinfunction "1_1") (pintype "passive"))
      (node (ref "JP6") (pin "2") (pinfunction "2_2") (pintype "passive"))
      (node (ref "JP6") (pin "39") (pinfunction "39_39") (pintype "passive"))
      (node (ref "JP6") (pin "40") (pinfunction "40_40") (pintype "passive"))
    )
  )
)
